# in_board.net
KiCad netlist of a schematic drawn in Altium Designer
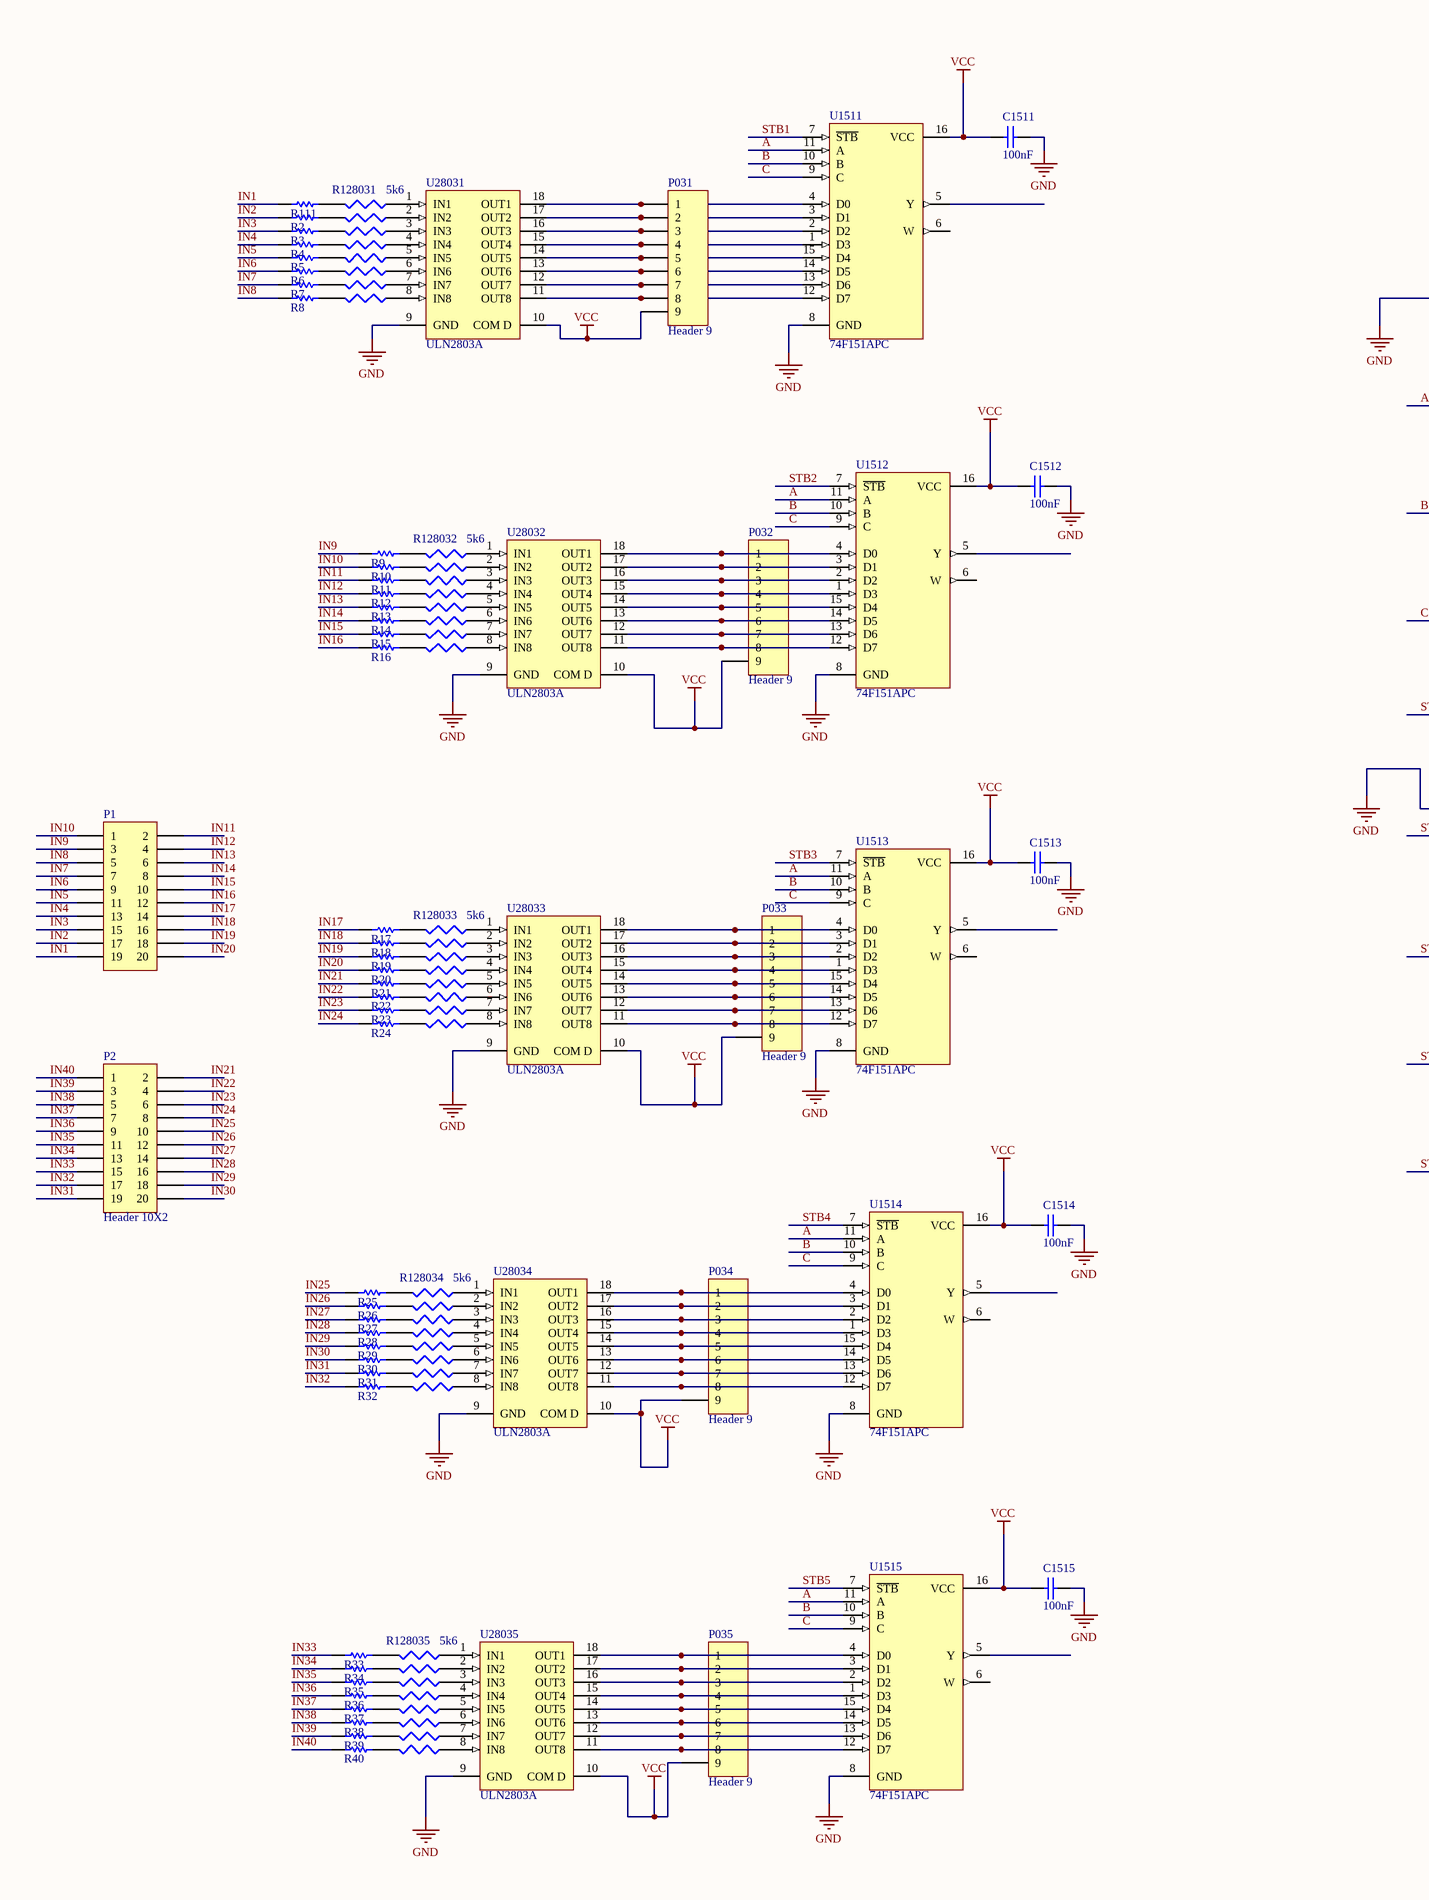
[diagram p0: in_board.SchDoc, left]
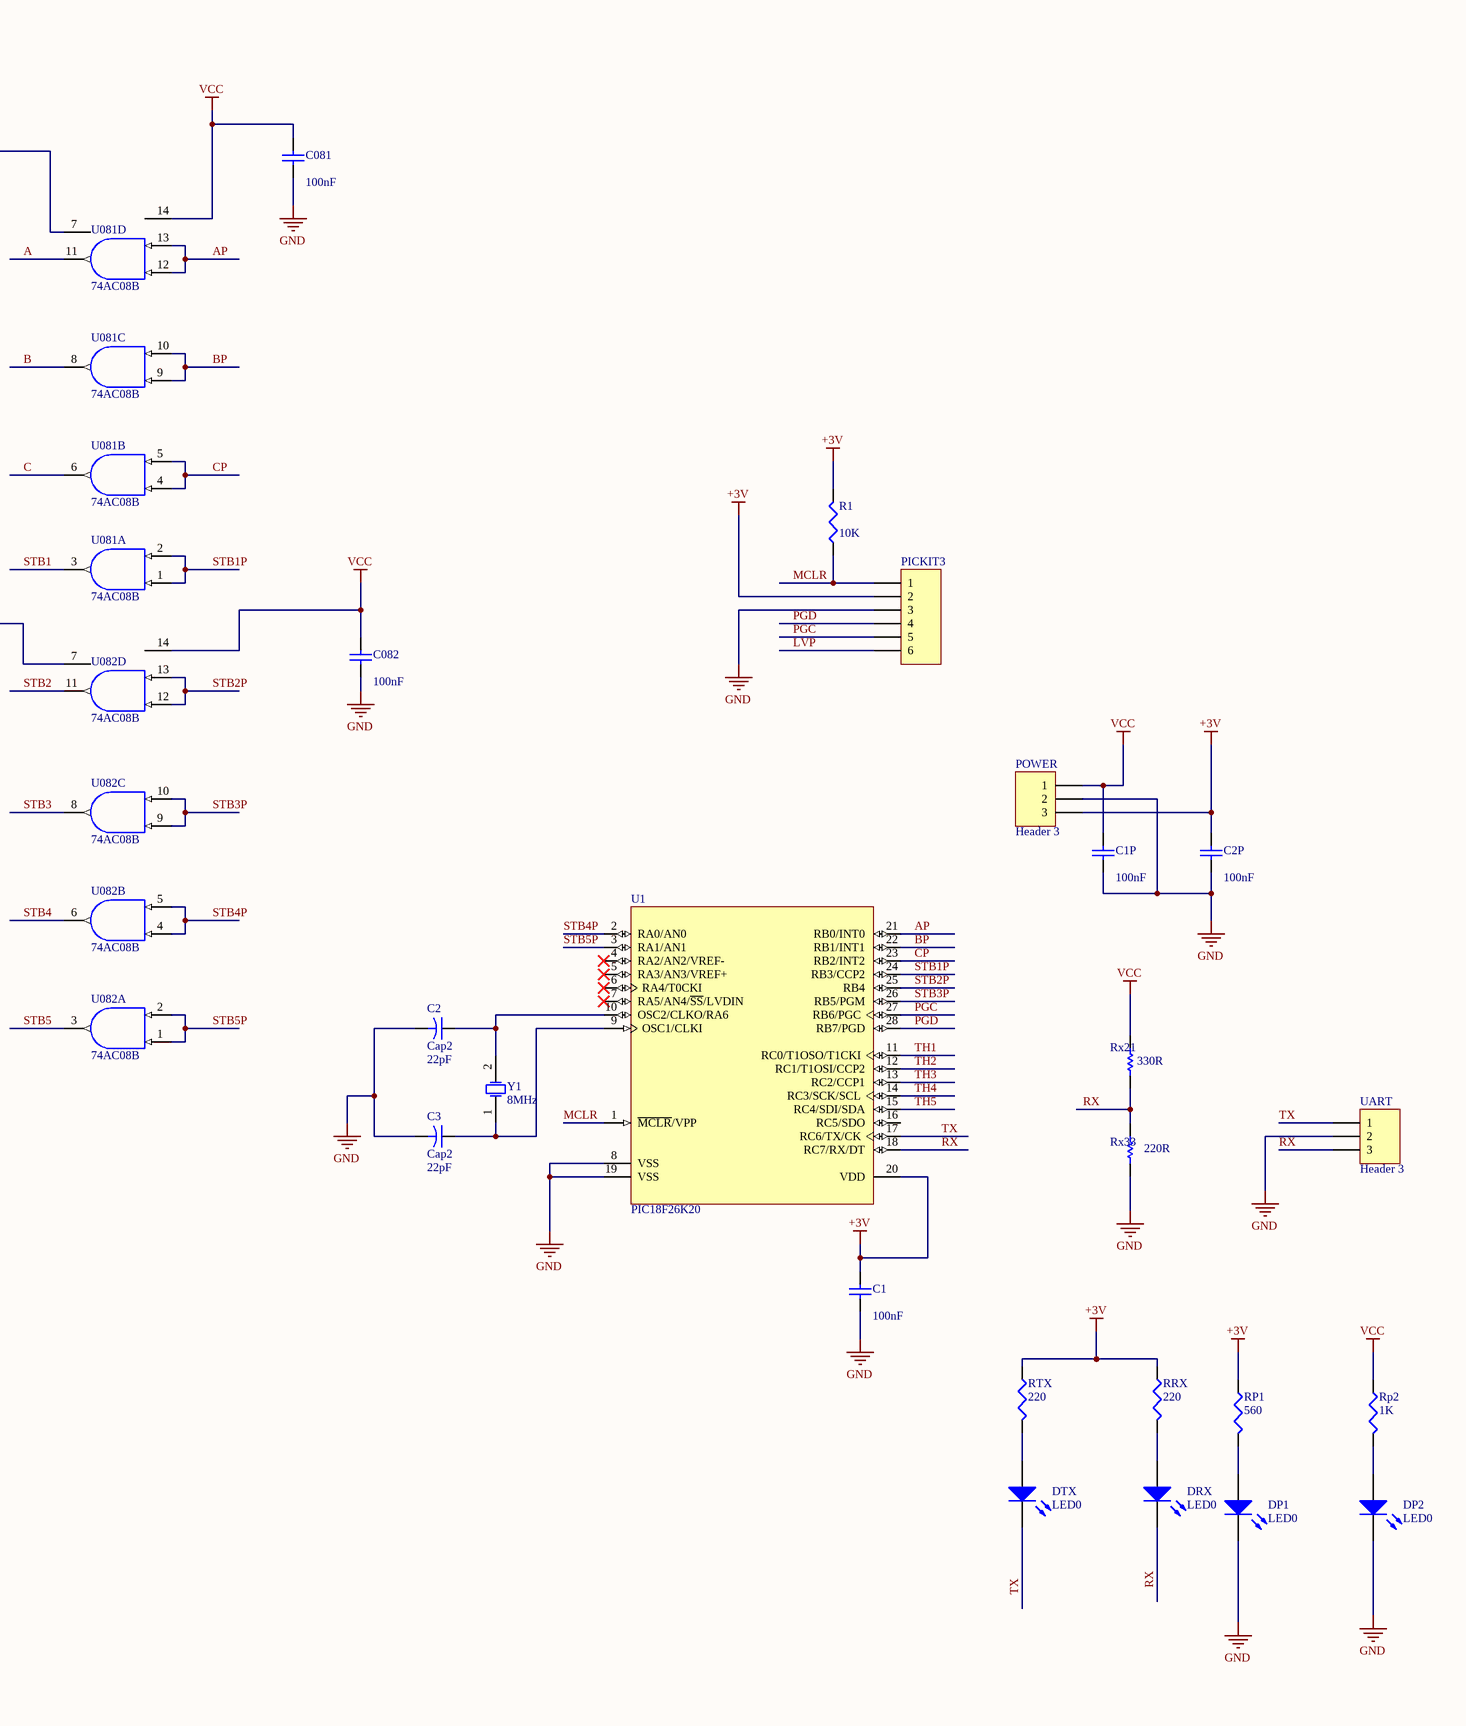
[diagram p1: in_board.SchDoc, right]

(export (version "E")
  (design (tool "Eeschema 10.0.6"))
  (components
    (comp (ref "C1")
      (value "100nF")
      (footprint "Device:tu_gom")
      (description "Capacitor")
      (fields (field (name "Comment") "Cap") (field (name "PUBLISHER") "Altium Limited"))
      (libsource (lib "Miscellaneous Devices") (part "Cap"))
    )
    (comp (ref "C1P")
      (value "100nF")
      (footprint "Device:tu_gom")
      (description "Capacitor")
      (fields (field (name "Comment") "Cap") (field (name "PUBLISHER") "Altium Limited"))
      (libsource (lib "Miscellaneous Devices") (part "Cap"))
    )
    (comp (ref "C2")
      (value "Cap2")
      (footprint "Device:tu_gom")
      (description "Capacitor")
      (fields (field (name "ALTIUM_VALUE") "22pF") (field (name "PUBLISHER") "Altium Limited"))
      (libsource (lib "Miscellaneous Devices") (part "Cap2"))
    )
    (comp (ref "C2P")
      (value "100nF")
      (footprint "Device:tu_gom")
      (description "Capacitor")
      (fields (field (name "Comment") "Cap") (field (name "PUBLISHER") "Altium Limited"))
      (libsource (lib "Miscellaneous Devices") (part "Cap"))
    )
    (comp (ref "C3")
      (value "Cap2")
      (footprint "Device:tu_gom")
      (description "Capacitor")
      (fields (field (name "ALTIUM_VALUE") "22pF") (field (name "PUBLISHER") "Altium Limited"))
      (libsource (lib "Miscellaneous Devices") (part "Cap2"))
    )
    (comp (ref "C081")
      (value "100nF")
      (footprint "Device:tu_gom")
      (description "Capacitor")
      (fields (field (name "Comment") "Cap") (field (name "PUBLISHER") "Altium Limited"))
      (libsource (lib "Miscellaneous Devices") (part "Cap"))
    )
    (comp (ref "C082")
      (value "100nF")
      (footprint "Device:tu_gom")
      (description "Capacitor")
      (fields (field (name "Comment") "Cap") (field (name "PUBLISHER") "Altium Limited"))
      (libsource (lib "Miscellaneous Devices") (part "Cap"))
    )
    (comp (ref "C1511")
      (value "100nF")
      (footprint "Device:tu_gom")
      (description "Capacitor")
      (fields (field (name "Comment") "Cap") (field (name "PUBLISHER") "Altium Limited"))
      (libsource (lib "Miscellaneous Devices") (part "Cap"))
    )
    (comp (ref "C1512")
      (value "100nF")
      (footprint "Device:tu_gom")
      (description "Capacitor")
      (fields (field (name "Comment") "Cap") (field (name "PUBLISHER") "Altium Limited"))
      (libsource (lib "Miscellaneous Devices") (part "Cap"))
    )
    (comp (ref "C1513")
      (value "100nF")
      (footprint "Device:tu_gom")
      (description "Capacitor")
      (fields (field (name "Comment") "Cap") (field (name "PUBLISHER") "Altium Limited"))
      (libsource (lib "Miscellaneous Devices") (part "Cap"))
    )
    (comp (ref "C1514")
      (value "100nF")
      (footprint "Device:tu_gom")
      (description "Capacitor")
      (fields (field (name "Comment") "Cap") (field (name "PUBLISHER") "Altium Limited"))
      (libsource (lib "Miscellaneous Devices") (part "Cap"))
    )
    (comp (ref "C1515")
      (value "100nF")
      (footprint "Device:tu_gom")
      (description "Capacitor")
      (fields (field (name "Comment") "Cap") (field (name "PUBLISHER") "Altium Limited"))
      (libsource (lib "Miscellaneous Devices") (part "Cap"))
    )
    (comp (ref "DP1")
      (value "LED0")
      (footprint "Device:LED_3")
      (description "Typical INFRARED GaAs LED")
      (fields (field (name "PUBLISHER") "Altium Limited"))
      (libsource (lib "Miscellaneous Devices") (part "LED0"))
    )
    (comp (ref "DP2")
      (value "LED0")
      (footprint "Device:LED_3")
      (description "Typical INFRARED GaAs LED")
      (fields (field (name "PUBLISHER") "Altium Limited"))
      (libsource (lib "Miscellaneous Devices") (part "LED0"))
    )
    (comp (ref "DRX")
      (value "LED0")
      (footprint "Device:LED_3")
      (description "Typical INFRARED GaAs LED")
      (fields (field (name "PUBLISHER") "Altium Limited"))
      (libsource (lib "Miscellaneous Devices") (part "LED0"))
    )
    (comp (ref "DTX")
      (value "LED0")
      (footprint "Device:LED_3")
      (description "Typical INFRARED GaAs LED")
      (fields (field (name "PUBLISHER") "Altium Limited"))
      (libsource (lib "Miscellaneous Devices") (part "LED0"))
    )
    (comp (ref "P1")
      (value "Header 10X2")
      (footprint "HDR2X10")
      (description "Header, 10-Pin, Dual row")
      (fields (field (name "PUBLISHER") "Altium Limited"))
      (libsource (lib "Miscellaneous Connectors") (part "Header 10X2"))
    )
    (comp (ref "P2")
      (value "Header 10X2")
      (footprint "HDR2X10")
      (description "Header, 10-Pin, Dual row")
      (fields (field (name "PUBLISHER") "Altium Limited"))
      (libsource (lib "Miscellaneous Connectors") (part "Header 10X2"))
    )
    (comp (ref "P031")
      (value "Header 9")
      (footprint "HDR1X9")
      (description "Header, 9-Pin")
      (fields (field (name "PUBLISHER") "Altium Limited"))
      (libsource (lib "Miscellaneous Connectors") (part "Header 9"))
    )
    (comp (ref "P032")
      (value "Header 9")
      (footprint "HDR1X9")
      (description "Header, 9-Pin")
      (fields (field (name "PUBLISHER") "Altium Limited"))
      (libsource (lib "Miscellaneous Connectors") (part "Header 9"))
    )
    (comp (ref "P033")
      (value "Header 9")
      (footprint "HDR1X9")
      (description "Header, 9-Pin")
      (fields (field (name "PUBLISHER") "Altium Limited"))
      (libsource (lib "Miscellaneous Connectors") (part "Header 9"))
    )
    (comp (ref "P034")
      (value "Header 9")
      (footprint "HDR1X9")
      (description "Header, 9-Pin")
      (fields (field (name "PUBLISHER") "Altium Limited"))
      (libsource (lib "Miscellaneous Connectors") (part "Header 9"))
    )
    (comp (ref "P035")
      (value "Header 9")
      (footprint "HDR1X9")
      (description "Header, 9-Pin")
      (fields (field (name "PUBLISHER") "Altium Limited"))
      (libsource (lib "Miscellaneous Connectors") (part "Header 9"))
    )
    (comp (ref "PICKIT3")
      (value "PICKIT3")
      (footprint "HDR1X6")
      (description "Header, 6-Pin")
      (fields (field (name "PUBLISHER") "Altium Limited"))
      (libsource (lib "Miscellaneous Connectors") (part "Header 6"))
    )
    (comp (ref "POWER")
      (value "Header 3")
      (footprint "Device:HEADER3")
      (description "Header, 3-Pin")
      (fields (field (name "PUBLISHER") "Altium Limited"))
      (libsource (lib "Miscellaneous Connectors") (part "Header 3"))
    )
    (comp (ref "R1")
      (value "10K")
      (footprint "Device:R_Nor")
      (description "Resistor")
      (fields (field (name "Comment") "Res3") (field (name "PUBLISHER") "Altium Limited"))
      (libsource (lib "Miscellaneous Devices") (part "Res3"))
    )
    (comp (ref "R2")
      (value "Res")
      (footprint "Device:R_Nor")
      (libsource (lib "Device_Component") (part "Res"))
    )
    (comp (ref "R3")
      (value "Res")
      (footprint "Device:R_Nor")
      (libsource (lib "Device_Component") (part "Res"))
    )
    (comp (ref "R4")
      (value "Res")
      (footprint "Device:R_Nor")
      (libsource (lib "Device_Component") (part "Res"))
    )
    (comp (ref "R5")
      (value "Res")
      (footprint "Device:R_Nor")
      (libsource (lib "Device_Component") (part "Res"))
    )
    (comp (ref "R6")
      (value "Res")
      (footprint "Device:R_Nor")
      (libsource (lib "Device_Component") (part "Res"))
    )
    (comp (ref "R7")
      (value "Res")
      (footprint "Device:R_Nor")
      (libsource (lib "Device_Component") (part "Res"))
    )
    (comp (ref "R8")
      (value "Res")
      (footprint "Device:R_Nor")
      (libsource (lib "Device_Component") (part "Res"))
    )
    (comp (ref "R9")
      (value "Res")
      (footprint "Device:R_Nor")
      (libsource (lib "Device_Component") (part "Res"))
    )
    (comp (ref "R10")
      (value "Res")
      (footprint "Device:R_Nor")
      (libsource (lib "Device_Component") (part "Res"))
    )
    (comp (ref "R11")
      (value "Res")
      (footprint "Device:R_Nor")
      (libsource (lib "Device_Component") (part "Res"))
    )
    (comp (ref "R12")
      (value "Res")
      (footprint "Device:R_Nor")
      (libsource (lib "Device_Component") (part "Res"))
    )
    (comp (ref "R13")
      (value "Res")
      (footprint "Device:R_Nor")
      (libsource (lib "Device_Component") (part "Res"))
    )
    (comp (ref "R14")
      (value "Res")
      (footprint "Device:R_Nor")
      (libsource (lib "Device_Component") (part "Res"))
    )
    (comp (ref "R15")
      (value "Res")
      (footprint "Device:R_Nor")
      (libsource (lib "Device_Component") (part "Res"))
    )
    (comp (ref "R16")
      (value "Res")
      (footprint "Device:R_Nor")
      (libsource (lib "Device_Component") (part "Res"))
    )
    (comp (ref "R17")
      (value "Res")
      (footprint "Device:R_Nor")
      (libsource (lib "Device_Component") (part "Res"))
    )
    (comp (ref "R18")
      (value "Res")
      (footprint "Device:R_Nor")
      (libsource (lib "Device_Component") (part "Res"))
    )
    (comp (ref "R19")
      (value "Res")
      (footprint "Device:R_Nor")
      (libsource (lib "Device_Component") (part "Res"))
    )
    (comp (ref "R20")
      (value "Res")
      (footprint "Device:R_Nor")
      (libsource (lib "Device_Component") (part "Res"))
    )
    (comp (ref "R21")
      (value "Res")
      (footprint "Device:R_Nor")
      (libsource (lib "Device_Component") (part "Res"))
    )
    (comp (ref "R22")
      (value "Res")
      (footprint "Device:R_Nor")
      (libsource (lib "Device_Component") (part "Res"))
    )
    (comp (ref "R23")
      (value "Res")
      (footprint "Device:R_Nor")
      (libsource (lib "Device_Component") (part "Res"))
    )
    (comp (ref "R24")
      (value "Res")
      (footprint "Device:R_Nor")
      (libsource (lib "Device_Component") (part "Res"))
    )
    (comp (ref "R25")
      (value "Res")
      (footprint "Device:R_Nor")
      (libsource (lib "Device_Component") (part "Res"))
    )
    (comp (ref "R26")
      (value "Res")
      (footprint "Device:R_Nor")
      (libsource (lib "Device_Component") (part "Res"))
    )
    (comp (ref "R27")
      (value "Res")
      (footprint "Device:R_Nor")
      (libsource (lib "Device_Component") (part "Res"))
    )
    (comp (ref "R28")
      (value "Res")
      (footprint "Device:R_Nor")
      (libsource (lib "Device_Component") (part "Res"))
    )
    (comp (ref "R29")
      (value "Res")
      (footprint "Device:R_Nor")
      (libsource (lib "Device_Component") (part "Res"))
    )
    (comp (ref "R30")
      (value "Res")
      (footprint "Device:R_Nor")
      (libsource (lib "Device_Component") (part "Res"))
    )
    (comp (ref "R31")
      (value "Res")
      (footprint "Device:R_Nor")
      (libsource (lib "Device_Component") (part "Res"))
    )
    (comp (ref "R32")
      (value "Res")
      (footprint "Device:R_Nor")
      (libsource (lib "Device_Component") (part "Res"))
    )
    (comp (ref "R33")
      (value "Res")
      (footprint "Device:R_Nor")
      (libsource (lib "Device_Component") (part "Res"))
    )
    (comp (ref "R34")
      (value "Res")
      (footprint "Device:R_Nor")
      (libsource (lib "Device_Component") (part "Res"))
    )
    (comp (ref "R35")
      (value "Res")
      (footprint "Device:R_Nor")
      (libsource (lib "Device_Component") (part "Res"))
    )
    (comp (ref "R36")
      (value "Res")
      (footprint "Device:R_Nor")
      (libsource (lib "Device_Component") (part "Res"))
    )
    (comp (ref "R37")
      (value "Res")
      (footprint "Device:R_Nor")
      (libsource (lib "Device_Component") (part "Res"))
    )
    (comp (ref "R38")
      (value "Res")
      (footprint "Device:R_Nor")
      (libsource (lib "Device_Component") (part "Res"))
    )
    (comp (ref "R39")
      (value "Res")
      (footprint "Device:R_Nor")
      (libsource (lib "Device_Component") (part "Res"))
    )
    (comp (ref "R40")
      (value "Res")
      (footprint "Device:R_Nor")
      (libsource (lib "Device_Component") (part "Res"))
    )
    (comp (ref "R111")
      (value "Res")
      (footprint "Device:R_Nor")
      (libsource (lib "Device_Component") (part "Res"))
    )
    (comp (ref "R42802")
      (value "Res3")
      (footprint "Device:R_Nor")
      (description "Resistor")
      (fields (field (name "PUBLISHER") "Altium Limited"))
      (libsource (lib "Miscellaneous Devices") (part "Res3"))
    )
    (comp (ref "R42803")
      (value "Res3")
      (footprint "Device:R_Nor")
      (description "Resistor")
      (fields (field (name "PUBLISHER") "Altium Limited"))
      (libsource (lib "Miscellaneous Devices") (part "Res3"))
    )
    (comp (ref "R42804")
      (value "Res3")
      (footprint "Device:R_Nor")
      (description "Resistor")
      (fields (field (name "PUBLISHER") "Altium Limited"))
      (libsource (lib "Miscellaneous Devices") (part "Res3"))
    )
    (comp (ref "R128031")
      (value "5k6")
      (footprint "Device:R_Nor")
      (description "Resistor")
      (fields (field (name "Comment") "Res3") (field (name "PUBLISHER") "Altium Limited"))
      (libsource (lib "Miscellaneous Devices") (part "Res3"))
    )
    (comp (ref "R128032")
      (value "5k6")
      (footprint "Device:R_Nor")
      (description "Resistor")
      (fields (field (name "Comment") "Res3") (field (name "PUBLISHER") "Altium Limited"))
      (libsource (lib "Miscellaneous Devices") (part "Res3"))
    )
    (comp (ref "R128033")
      (value "5k6")
      (footprint "Device:R_Nor")
      (description "Resistor")
      (fields (field (name "Comment") "Res3") (field (name "PUBLISHER") "Altium Limited"))
      (libsource (lib "Miscellaneous Devices") (part "Res3"))
    )
    (comp (ref "R128034")
      (value "5k6")
      (footprint "Device:R_Nor")
      (description "Resistor")
      (fields (field (name "Comment") "Res3") (field (name "PUBLISHER") "Altium Limited"))
      (libsource (lib "Miscellaneous Devices") (part "Res3"))
    )
    (comp (ref "R128035")
      (value "5k6")
      (footprint "Device:R_Nor")
      (description "Resistor")
      (fields (field (name "Comment") "Res3") (field (name "PUBLISHER") "Altium Limited"))
      (libsource (lib "Miscellaneous Devices") (part "Res3"))
    )
    (comp (ref "R228031")
      (value "Res3")
      (footprint "Device:R_Nor")
      (description "Resistor")
      (fields (field (name "PUBLISHER") "Altium Limited"))
      (libsource (lib "Miscellaneous Devices") (part "Res3"))
    )
    (comp (ref "R228032")
      (value "Res3")
      (footprint "Device:R_Nor")
      (description "Resistor")
      (fields (field (name "PUBLISHER") "Altium Limited"))
      (libsource (lib "Miscellaneous Devices") (part "Res3"))
    )
    (comp (ref "R228033")
      (value "Res3")
      (footprint "Device:R_Nor")
      (description "Resistor")
      (fields (field (name "PUBLISHER") "Altium Limited"))
      (libsource (lib "Miscellaneous Devices") (part "Res3"))
    )
    (comp (ref "R228034")
      (value "Res3")
      (footprint "Device:R_Nor")
      (description "Resistor")
      (fields (field (name "PUBLISHER") "Altium Limited"))
      (libsource (lib "Miscellaneous Devices") (part "Res3"))
    )
    (comp (ref "R228035")
      (value "Res3")
      (footprint "Device:R_Nor")
      (description "Resistor")
      (fields (field (name "PUBLISHER") "Altium Limited"))
      (libsource (lib "Miscellaneous Devices") (part "Res3"))
    )
    (comp (ref "R328031")
      (value "Res3")
      (footprint "Device:R_Nor")
      (description "Resistor")
      (fields (field (name "PUBLISHER") "Altium Limited"))
      (libsource (lib "Miscellaneous Devices") (part "Res3"))
    )
    (comp (ref "R328032")
      (value "Res3")
      (footprint "Device:R_Nor")
      (description "Resistor")
      (fields (field (name "PUBLISHER") "Altium Limited"))
      (libsource (lib "Miscellaneous Devices") (part "Res3"))
    )
    (comp (ref "R328033")
      (value "Res3")
      (footprint "Device:R_Nor")
      (description "Resistor")
      (fields (field (name "PUBLISHER") "Altium Limited"))
      (libsource (lib "Miscellaneous Devices") (part "Res3"))
    )
    (comp (ref "R328034")
      (value "Res3")
      (footprint "Device:R_Nor")
      (description "Resistor")
      (fields (field (name "PUBLISHER") "Altium Limited"))
      (libsource (lib "Miscellaneous Devices") (part "Res3"))
    )
    (comp (ref "R328035")
      (value "Res3")
      (footprint "Device:R_Nor")
      (description "Resistor")
      (fields (field (name "PUBLISHER") "Altium Limited"))
      (libsource (lib "Miscellaneous Devices") (part "Res3"))
    )
    (comp (ref "R428031")
      (value "Res3")
      (footprint "Device:R_Nor")
      (description "Resistor")
      (fields (field (name "PUBLISHER") "Altium Limited"))
      (libsource (lib "Miscellaneous Devices") (part "Res3"))
    )
    (comp (ref "R428035")
      (value "Res3")
      (footprint "Device:R_Nor")
      (description "Resistor")
      (fields (field (name "PUBLISHER") "Altium Limited"))
      (libsource (lib "Miscellaneous Devices") (part "Res3"))
    )
    (comp (ref "R528031")
      (value "Res3")
      (footprint "Device:R_Nor")
      (description "Resistor")
      (fields (field (name "PUBLISHER") "Altium Limited"))
      (libsource (lib "Miscellaneous Devices") (part "Res3"))
    )
    (comp (ref "R528032")
      (value "Res3")
      (footprint "Device:R_Nor")
      (description "Resistor")
      (fields (field (name "PUBLISHER") "Altium Limited"))
      (libsource (lib "Miscellaneous Devices") (part "Res3"))
    )
    (comp (ref "R528033")
      (value "Res3")
      (footprint "Device:R_Nor")
      (description "Resistor")
      (fields (field (name "PUBLISHER") "Altium Limited"))
      (libsource (lib "Miscellaneous Devices") (part "Res3"))
    )
    (comp (ref "R528034")
      (value "Res3")
      (footprint "Device:R_Nor")
      (description "Resistor")
      (fields (field (name "PUBLISHER") "Altium Limited"))
      (libsource (lib "Miscellaneous Devices") (part "Res3"))
    )
    (comp (ref "R528035")
      (value "Res3")
      (footprint "Device:R_Nor")
      (description "Resistor")
      (fields (field (name "PUBLISHER") "Altium Limited"))
      (libsource (lib "Miscellaneous Devices") (part "Res3"))
    )
    (comp (ref "R628031")
      (value "Res3")
      (footprint "Device:R_Nor")
      (description "Resistor")
      (fields (field (name "PUBLISHER") "Altium Limited"))
      (libsource (lib "Miscellaneous Devices") (part "Res3"))
    )
    (comp (ref "R628032")
      (value "Res3")
      (footprint "Device:R_Nor")
      (description "Resistor")
      (fields (field (name "PUBLISHER") "Altium Limited"))
      (libsource (lib "Miscellaneous Devices") (part "Res3"))
    )
    (comp (ref "R628033")
      (value "Res3")
      (footprint "Device:R_Nor")
      (description "Resistor")
      (fields (field (name "PUBLISHER") "Altium Limited"))
      (libsource (lib "Miscellaneous Devices") (part "Res3"))
    )
    (comp (ref "R628034")
      (value "Res3")
      (footprint "Device:R_Nor")
      (description "Resistor")
      (fields (field (name "PUBLISHER") "Altium Limited"))
      (libsource (lib "Miscellaneous Devices") (part "Res3"))
    )
    (comp (ref "R628035")
      (value "Res3")
      (footprint "Device:R_Nor")
      (description "Resistor")
      (fields (field (name "PUBLISHER") "Altium Limited"))
      (libsource (lib "Miscellaneous Devices") (part "Res3"))
    )
    (comp (ref "R728031")
      (value "Res3")
      (footprint "Device:R_Nor")
      (description "Resistor")
      (fields (field (name "PUBLISHER") "Altium Limited"))
      (libsource (lib "Miscellaneous Devices") (part "Res3"))
    )
    (comp (ref "R728032")
      (value "Res3")
      (footprint "Device:R_Nor")
      (description "Resistor")
      (fields (field (name "PUBLISHER") "Altium Limited"))
      (libsource (lib "Miscellaneous Devices") (part "Res3"))
    )
    (comp (ref "R728033")
      (value "Res3")
      (footprint "Device:R_Nor")
      (description "Resistor")
      (fields (field (name "PUBLISHER") "Altium Limited"))
      (libsource (lib "Miscellaneous Devices") (part "Res3"))
    )
    (comp (ref "R728034")
      (value "Res3")
      (footprint "Device:R_Nor")
      (description "Resistor")
      (fields (field (name "PUBLISHER") "Altium Limited"))
      (libsource (lib "Miscellaneous Devices") (part "Res3"))
    )
    (comp (ref "R728035")
      (value "Res3")
      (footprint "Device:R_Nor")
      (description "Resistor")
      (fields (field (name "PUBLISHER") "Altium Limited"))
      (libsource (lib "Miscellaneous Devices") (part "Res3"))
    )
    (comp (ref "R828031")
      (value "Res3")
      (footprint "Device:R_Nor")
      (description "Resistor")
      (fields (field (name "PUBLISHER") "Altium Limited"))
      (libsource (lib "Miscellaneous Devices") (part "Res3"))
    )
    (comp (ref "R828032")
      (value "Res3")
      (footprint "Device:R_Nor")
      (description "Resistor")
      (fields (field (name "PUBLISHER") "Altium Limited"))
      (libsource (lib "Miscellaneous Devices") (part "Res3"))
    )
    (comp (ref "R828033")
      (value "Res3")
      (footprint "Device:R_Nor")
      (description "Resistor")
      (fields (field (name "PUBLISHER") "Altium Limited"))
      (libsource (lib "Miscellaneous Devices") (part "Res3"))
    )
    (comp (ref "R828034")
      (value "Res3")
      (footprint "Device:R_Nor")
      (description "Resistor")
      (fields (field (name "PUBLISHER") "Altium Limited"))
      (libsource (lib "Miscellaneous Devices") (part "Res3"))
    )
    (comp (ref "R828035")
      (value "Res3")
      (footprint "Device:R_Nor")
      (description "Resistor")
      (fields (field (name "PUBLISHER") "Altium Limited"))
      (libsource (lib "Miscellaneous Devices") (part "Res3"))
    )
    (comp (ref "RP1")
      (value "560")
      (footprint "Device:R_Nor")
      (description "Resistor")
      (fields (field (name "Comment") "Res3") (field (name "PUBLISHER") "Altium Limited"))
      (libsource (lib "Miscellaneous Devices") (part "Res3"))
    )
    (comp (ref "Rp2")
      (value "1K")
      (footprint "Device:R_Nor")
      (description "Resistor")
      (fields (field (name "Comment") "Res3") (field (name "PUBLISHER") "Altium Limited"))
      (libsource (lib "Miscellaneous Devices") (part "Res3"))
    )
    (comp (ref "RRX")
      (value "220")
      (footprint "Device:R_Nor")
      (description "Resistor")
      (fields (field (name "Comment") "Res3") (field (name "PUBLISHER") "Altium Limited"))
      (libsource (lib "Miscellaneous Devices") (part "Res3"))
    )
    (comp (ref "RTX")
      (value "220")
      (footprint "Device:R_Nor")
      (description "Resistor")
      (fields (field (name "Comment") "Res3") (field (name "PUBLISHER") "Altium Limited"))
      (libsource (lib "Miscellaneous Devices") (part "Res3"))
    )
    (comp (ref "Rx21")
      (value "330R")
      (footprint "Device:R_Nor")
      (libsource (lib "Device_Component") (part "Res"))
    )
    (comp (ref "Rx33")
      (value "220R")
      (footprint "Device:R_Nor")
      (libsource (lib "Device_Component") (part "Res"))
    )
    (comp (ref "U1")
      (value "PIC18F26K20")
      (footprint "SOIC300-28_N")
      (fields (field (name "PUBLISHER") "Altium Limited"))
      (libsource (lib "Microchip Microcontroller 8-Bit PIC18") (part "PIC18F242-E/SO"))
    )
    (comp (ref "U081")
      (value "74AC08B")
      (footprint "DIP14")
      (description "Quad 2-Input AND Gate")
      (fields (field (name "PUBLISHER") "Altium Limited"))
      (libsource (lib "ST Logic Gate") (part "74AC08B"))
    )
    (comp (ref "U082")
      (value "74AC08B")
      (footprint "DIP14")
      (description "Quad 2-Input AND Gate")
      (fields (field (name "PUBLISHER") "Altium Limited"))
      (libsource (lib "ST Logic Gate") (part "74AC08B"))
    )
    (comp (ref "U1511")
      (value "74F151APC")
      (footprint "N16E")
      (description "8-Input Multiplexer")
      (fields (field (name "PUBLISHER") "Altium Limited"))
      (libsource (lib "NSC Logic Multiplexer") (part "74F151APC"))
    )
    (comp (ref "U1512")
      (value "74F151APC")
      (footprint "N16E")
      (description "8-Input Multiplexer")
      (fields (field (name "PUBLISHER") "Altium Limited"))
      (libsource (lib "NSC Logic Multiplexer") (part "74F151APC"))
    )
    (comp (ref "U1513")
      (value "74F151APC")
      (footprint "N16E")
      (description "8-Input Multiplexer")
      (fields (field (name "PUBLISHER") "Altium Limited"))
      (libsource (lib "NSC Logic Multiplexer") (part "74F151APC"))
    )
    (comp (ref "U1514")
      (value "74F151APC")
      (footprint "N16E")
      (description "8-Input Multiplexer")
      (fields (field (name "PUBLISHER") "Altium Limited"))
      (libsource (lib "NSC Logic Multiplexer") (part "74F151APC"))
    )
    (comp (ref "U1515")
      (value "74F151APC")
      (footprint "N16E")
      (description "8-Input Multiplexer")
      (fields (field (name "PUBLISHER") "Altium Limited"))
      (libsource (lib "NSC Logic Multiplexer") (part "74F151APC"))
    )
    (comp (ref "U28031")
      (value "ULN2803A")
      (footprint "DIP18")
      (description "Eight Darlington Array")
      (fields (field (name "PUBLISHER") "Altium Limited"))
      (libsource (lib "ST Interface Darlington Driver") (part "ULN2803A"))
    )
    (comp (ref "U28032")
      (value "ULN2803A")
      (footprint "DIP18")
      (description "Eight Darlington Array")
      (fields (field (name "PUBLISHER") "Altium Limited"))
      (libsource (lib "ST Interface Darlington Driver") (part "ULN2803A"))
    )
    (comp (ref "U28033")
      (value "ULN2803A")
      (footprint "DIP18")
      (description "Eight Darlington Array")
      (fields (field (name "PUBLISHER") "Altium Limited"))
      (libsource (lib "ST Interface Darlington Driver") (part "ULN2803A"))
    )
    (comp (ref "U28034")
      (value "ULN2803A")
      (footprint "DIP18")
      (description "Eight Darlington Array")
      (fields (field (name "PUBLISHER") "Altium Limited"))
      (libsource (lib "ST Interface Darlington Driver") (part "ULN2803A"))
    )
    (comp (ref "U28035")
      (value "ULN2803A")
      (footprint "DIP18")
      (description "Eight Darlington Array")
      (fields (field (name "PUBLISHER") "Altium Limited"))
      (libsource (lib "ST Interface Darlington Driver") (part "ULN2803A"))
    )
    (comp (ref "UART")
      (value "Header 3")
      (footprint "Device:Coc3_15A")
      (description "Header, 3-Pin")
      (fields (field (name "PUBLISHER") "Altium Limited"))
      (libsource (lib "") (part "Header 3_1"))
    )
    (comp (ref "Y1")
      (value "8MHz")
      (footprint "Device:Xtal12M")
      (description "Crystal Oscillator")
      (fields (field (name "PUBLISHER") "Altium Limited"))
      (libsource (lib "Miscellaneous Devices") (part "XTAL"))
    )
  )
  (nets
    (net (code "1") (name "+3V") (class "Default")
      (node (ref "C1") (pin "1") (pinfunction "1_1") (pintype "passive"))
      (node (ref "C2P") (pin "1") (pinfunction "1_1") (pintype "passive"))
      (node (ref "PICKIT3") (pin "2") (pinfunction "2_2") (pintype "passive"))
      (node (ref "POWER") (pin "3") (pinfunction "3_3") (pintype "passive"))
      (node (ref "R1") (pin "2") (pinfunction "2_2") (pintype "passive"))
      (node (ref "RP1") (pin "1") (pinfunction "1_1") (pintype "passive"))
      (node (ref "RRX") (pin "1") (pinfunction "1_1") (pintype "passive"))
      (node (ref "RTX") (pin "1") (pinfunction "1_1") (pintype "passive"))
      (node (ref "U1") (pin "20") (pinfunction "VDD_20") (pintype "power_in"))
    )
    (net (code "2") (name "/A") (class "Default")
      (node (ref "U081") (pin "11") (pinfunction "Y_11") (pintype "output"))
      (node (ref "U1511") (pin "11") (pinfunction "A_11") (pintype "input"))
      (node (ref "U1512") (pin "11") (pinfunction "A_11") (pintype "input"))
      (node (ref "U1513") (pin "11") (pinfunction "A_11") (pintype "input"))
      (node (ref "U1514") (pin "11") (pinfunction "A_11") (pintype "input"))
      (node (ref "U1515") (pin "11") (pinfunction "A_11") (pintype "input"))
    )
    (net (code "3") (name "/AP") (class "Default")
      (node (ref "U081") (pin "12") (pinfunction "A_12") (pintype "input"))
      (node (ref "U081") (pin "13") (pinfunction "B_13") (pintype "input"))
      (node (ref "U1") (pin "21") (pinfunction "RB0/INT0_21") (pintype "bidirectional"))
    )
    (net (code "4") (name "/B") (class "Default")
      (node (ref "U081") (pin "8") (pinfunction "Y_8") (pintype "output"))
      (node (ref "U1511") (pin "10") (pinfunction "B_10") (pintype "input"))
      (node (ref "U1512") (pin "10") (pinfunction "B_10") (pintype "input"))
      (node (ref "U1513") (pin "10") (pinfunction "B_10") (pintype "input"))
      (node (ref "U1514") (pin "10") (pinfunction "B_10") (pintype "input"))
      (node (ref "U1515") (pin "10") (pinfunction "B_10") (pintype "input"))
    )
    (net (code "5") (name "/BP") (class "Default")
      (node (ref "U081") (pin "10") (pinfunction "B_10") (pintype "input"))
      (node (ref "U081") (pin "9") (pinfunction "A_9") (pintype "input"))
      (node (ref "U1") (pin "22") (pinfunction "RB1/INT1_22") (pintype "bidirectional"))
    )
    (net (code "6") (name "/C") (class "Default")
      (node (ref "U081") (pin "6") (pinfunction "Y_6") (pintype "output"))
      (node (ref "U1511") (pin "9") (pinfunction "C_9") (pintype "input"))
      (node (ref "U1512") (pin "9") (pinfunction "C_9") (pintype "input"))
      (node (ref "U1513") (pin "9") (pinfunction "C_9") (pintype "input"))
      (node (ref "U1514") (pin "9") (pinfunction "C_9") (pintype "input"))
      (node (ref "U1515") (pin "9") (pinfunction "C_9") (pintype "input"))
    )
    (net (code "7") (name "/CP") (class "Default")
      (node (ref "U081") (pin "4") (pinfunction "A_4") (pintype "input"))
      (node (ref "U081") (pin "5") (pinfunction "B_5") (pintype "input"))
      (node (ref "U1") (pin "23") (pinfunction "RB2/INT2_23") (pintype "bidirectional"))
    )
    (net (code "8") (name "/IN1") (class "Default")
      (node (ref "P1") (pin "19") (pinfunction "19_19") (pintype "passive"))
      (node (ref "R111") (pin "1") (pinfunction "1_1") (pintype "passive"))
    )
    (net (code "9") (name "/IN2") (class "Default")
      (node (ref "P1") (pin "17") (pinfunction "17_17") (pintype "passive"))
      (node (ref "R2") (pin "1") (pinfunction "1_1") (pintype "passive"))
    )
    (net (code "10") (name "/IN3") (class "Default")
      (node (ref "P1") (pin "15") (pinfunction "15_15") (pintype "passive"))
      (node (ref "R3") (pin "1") (pinfunction "1_1") (pintype "passive"))
    )
    (net (code "11") (name "/IN4") (class "Default")
      (node (ref "P1") (pin "13") (pinfunction "13_13") (pintype "passive"))
      (node (ref "R4") (pin "1") (pinfunction "1_1") (pintype "passive"))
    )
    (net (code "12") (name "/IN5") (class "Default")
      (node (ref "P1") (pin "11") (pinfunction "11_11") (pintype "passive"))
      (node (ref "R5") (pin "1") (pinfunction "1_1") (pintype "passive"))
    )
    (net (code "13") (name "/IN6") (class "Default")
      (node (ref "P1") (pin "9") (pinfunction "9_9") (pintype "passive"))
      (node (ref "R6") (pin "1") (pinfunction "1_1") (pintype "passive"))
    )
    (net (code "14") (name "/IN7") (class "Default")
      (node (ref "P1") (pin "7") (pinfunction "7_7") (pintype "passive"))
      (node (ref "R7") (pin "1") (pinfunction "1_1") (pintype "passive"))
    )
    (net (code "15") (name "/IN8") (class "Default")
      (node (ref "P1") (pin "5") (pinfunction "5_5") (pintype "passive"))
      (node (ref "R8") (pin "1") (pinfunction "1_1") (pintype "passive"))
    )
    (net (code "16") (name "/IN9") (class "Default")
      (node (ref "P1") (pin "3") (pinfunction "3_3") (pintype "passive"))
      (node (ref "R9") (pin "1") (pinfunction "1_1") (pintype "passive"))
    )
    (net (code "17") (name "/IN10") (class "Default")
      (node (ref "P1") (pin "1") (pinfunction "1_1") (pintype "passive"))
      (node (ref "R10") (pin "1") (pinfunction "1_1") (pintype "passive"))
    )
    (net (code "18") (name "/IN11") (class "Default")
      (node (ref "P1") (pin "2") (pinfunction "2_2") (pintype "passive"))
      (node (ref "R11") (pin "1") (pinfunction "1_1") (pintype "passive"))
    )
    (net (code "19") (name "/IN12") (class "Default")
      (node (ref "P1") (pin "4") (pinfunction "4_4") (pintype "passive"))
      (node (ref "R12") (pin "1") (pinfunction "1_1") (pintype "passive"))
    )
    (net (code "20") (name "/IN13") (class "Default")
      (node (ref "P1") (pin "6") (pinfunction "6_6") (pintype "passive"))
      (node (ref "R13") (pin "1") (pinfunction "1_1") (pintype "passive"))
    )
    (net (code "21") (name "/IN14") (class "Default")
      (node (ref "P1") (pin "8") (pinfunction "8_8") (pintype "passive"))
      (node (ref "R14") (pin "1") (pinfunction "1_1") (pintype "passive"))
    )
    (net (code "22") (name "/IN15") (class "Default")
      (node (ref "P1") (pin "10") (pinfunction "10_10") (pintype "passive"))
      (node (ref "R15") (pin "1") (pinfunction "1_1") (pintype "passive"))
    )
    (net (code "23") (name "/IN16") (class "Default")
      (node (ref "P1") (pin "12") (pinfunction "12_12") (pintype "passive"))
      (node (ref "R16") (pin "1") (pinfunction "1_1") (pintype "passive"))
    )
    (net (code "24") (name "/IN17") (class "Default")
      (node (ref "P1") (pin "14") (pinfunction "14_14") (pintype "passive"))
      (node (ref "R17") (pin "1") (pinfunction "1_1") (pintype "passive"))
    )
    (net (code "25") (name "/IN18") (class "Default")
      (node (ref "P1") (pin "16") (pinfunction "16_16") (pintype "passive"))
      (node (ref "R18") (pin "1") (pinfunction "1_1") (pintype "passive"))
    )
    (net (code "26") (name "/IN19") (class "Default")
      (node (ref "P1") (pin "18") (pinfunction "18_18") (pintype "passive"))
      (node (ref "R19") (pin "1") (pinfunction "1_1") (pintype "passive"))
    )
    (net (code "27") (name "/IN20") (class "Default")
      (node (ref "P1") (pin "20") (pinfunction "20_20") (pintype "passive"))
      (node (ref "R20") (pin "1") (pinfunction "1_1") (pintype "passive"))
    )
    (net (code "28") (name "/IN21") (class "Default")
      (node (ref "P2") (pin "2") (pinfunction "2_2") (pintype "passive"))
      (node (ref "R21") (pin "1") (pinfunction "1_1") (pintype "passive"))
    )
    (net (code "29") (name "/IN22") (class "Default")
      (node (ref "P2") (pin "4") (pinfunction "4_4") (pintype "passive"))
      (node (ref "R22") (pin "1") (pinfunction "1_1") (pintype "passive"))
    )
    (net (code "30") (name "/IN23") (class "Default")
      (node (ref "P2") (pin "6") (pinfunction "6_6") (pintype "passive"))
      (node (ref "R23") (pin "1") (pinfunction "1_1") (pintype "passive"))
    )
    (net (code "31") (name "/IN24") (class "Default")
      (node (ref "P2") (pin "8") (pinfunction "8_8") (pintype "passive"))
      (node (ref "R24") (pin "1") (pinfunction "1_1") (pintype "passive"))
    )
    (net (code "32") (name "/IN25") (class "Default")
      (node (ref "P2") (pin "10") (pinfunction "10_10") (pintype "passive"))
      (node (ref "R25") (pin "1") (pinfunction "1_1") (pintype "passive"))
    )
    (net (code "33") (name "/IN26") (class "Default")
      (node (ref "P2") (pin "12") (pinfunction "12_12") (pintype "passive"))
      (node (ref "R26") (pin "1") (pinfunction "1_1") (pintype "passive"))
    )
    (net (code "34") (name "/IN27") (class "Default")
      (node (ref "P2") (pin "14") (pinfunction "14_14") (pintype "passive"))
      (node (ref "R27") (pin "1") (pinfunction "1_1") (pintype "passive"))
    )
    (net (code "35") (name "/IN28") (class "Default")
      (node (ref "P2") (pin "16") (pinfunction "16_16") (pintype "passive"))
      (node (ref "R28") (pin "1") (pinfunction "1_1") (pintype "passive"))
    )
    (net (code "36") (name "/IN29") (class "Default")
      (node (ref "P2") (pin "18") (pinfunction "18_18") (pintype "passive"))
      (node (ref "R29") (pin "1") (pinfunction "1_1") (pintype "passive"))
    )
    (net (code "37") (name "/IN30") (class "Default")
      (node (ref "P2") (pin "20") (pinfunction "20_20") (pintype "passive"))
      (node (ref "R30") (pin "1") (pinfunction "1_1") (pintype "passive"))
    )
    (net (code "38") (name "/IN31") (class "Default")
      (node (ref "P2") (pin "19") (pinfunction "19_19") (pintype "passive"))
      (node (ref "R31") (pin "1") (pinfunction "1_1") (pintype "passive"))
    )
    (net (code "39") (name "/IN32") (class "Default")
      (node (ref "P2") (pin "17") (pinfunction "17_17") (pintype "passive"))
      (node (ref "R32") (pin "1") (pinfunction "1_1") (pintype "passive"))
    )
    (net (code "40") (name "/IN33") (class "Default")
      (node (ref "P2") (pin "15") (pinfunction "15_15") (pintype "passive"))
      (node (ref "R33") (pin "1") (pinfunction "1_1") (pintype "passive"))
    )
    (net (code "41") (name "/IN34") (class "Default")
      (node (ref "P2") (pin "13") (pinfunction "13_13") (pintype "passive"))
      (node (ref "R34") (pin "1") (pinfunction "1_1") (pintype "passive"))
    )
    (net (code "42") (name "/IN35") (class "Default")
      (node (ref "P2") (pin "11") (pinfunction "11_11") (pintype "passive"))
      (node (ref "R35") (pin "1") (pinfunction "1_1") (pintype "passive"))
    )
    (net (code "43") (name "/IN36") (class "Default")
      (node (ref "P2") (pin "9") (pinfunction "9_9") (pintype "passive"))
      (node (ref "R36") (pin "1") (pinfunction "1_1") (pintype "passive"))
    )
    (net (code "44") (name "/IN37") (class "Default")
      (node (ref "P2") (pin "7") (pinfunction "7_7") (pintype "passive"))
      (node (ref "R37") (pin "1") (pinfunction "1_1") (pintype "passive"))
    )
    (net (code "45") (name "/IN38") (class "Default")
      (node (ref "P2") (pin "5") (pinfunction "5_5") (pintype "passive"))
      (node (ref "R38") (pin "1") (pinfunction "1_1") (pintype "passive"))
    )
    (net (code "46") (name "/IN39") (class "Default")
      (node (ref "P2") (pin "3") (pinfunction "3_3") (pintype "passive"))
      (node (ref "R39") (pin "1") (pinfunction "1_1") (pintype "passive"))
    )
    (net (code "47") (name "/IN40") (class "Default")
      (node (ref "P2") (pin "1") (pinfunction "1_1") (pintype "passive"))
      (node (ref "R40") (pin "1") (pinfunction "1_1") (pintype "passive"))
    )
    (net (code "48") (name "/LVP") (class "Default")
      (node (ref "PICKIT3") (pin "6") (pinfunction "6_6") (pintype "passive"))
    )
    (net (code "49") (name "/MCLR") (class "Default")
      (node (ref "PICKIT3") (pin "1") (pinfunction "1_1") (pintype "passive"))
      (node (ref "R1") (pin "1") (pinfunction "1_1") (pintype "passive"))
      (node (ref "U1") (pin "1") (pinfunction "~{MCLR}/VPP_1") (pintype "input"))
    )
    (net (code "50") (name "/PGC") (class "Default")
      (node (ref "PICKIT3") (pin "5") (pinfunction "5_5") (pintype "passive"))
      (node (ref "U1") (pin "27") (pinfunction "RB6/PGC_27") (pintype "bidirectional"))
    )
    (net (code "51") (name "/PGD") (class "Default")
      (node (ref "PICKIT3") (pin "4") (pinfunction "4_4") (pintype "passive"))
      (node (ref "U1") (pin "28") (pinfunction "RB7/PGD_28") (pintype "bidirectional"))
    )
    (net (code "52") (name "/RX") (class "Default")
      (node (ref "DRX") (pin "2") (pinfunction "K_2") (pintype "passive"))
      (node (ref "Rx21") (pin "1") (pinfunction "1_1") (pintype "passive"))
      (node (ref "Rx33") (pin "2") (pinfunction "2_2") (pintype "passive"))
      (node (ref "U1") (pin "18") (pinfunction "RC7/RX/DT_18") (pintype "bidirectional"))
      (node (ref "UART") (pin "3") (pinfunction "3_3") (pintype "passive"))
    )
    (net (code "53") (name "/STB1") (class "Default")
      (node (ref "U081") (pin "3") (pinfunction "Y_3") (pintype "output"))
      (node (ref "U1511") (pin "7") (pinfunction "~{STB}_7") (pintype "input"))
    )
    (net (code "54") (name "/STB1P") (class "Default")
      (node (ref "U081") (pin "1") (pinfunction "A_1") (pintype "input"))
      (node (ref "U081") (pin "2") (pinfunction "B_2") (pintype "input"))
      (node (ref "U1") (pin "24") (pinfunction "RB3/CCP2_24") (pintype "bidirectional"))
    )
    (net (code "55") (name "/STB2") (class "Default")
      (node (ref "U082") (pin "11") (pinfunction "Y_11") (pintype "output"))
      (node (ref "U1512") (pin "7") (pinfunction "~{STB}_7") (pintype "input"))
    )
    (net (code "56") (name "/STB2P") (class "Default")
      (node (ref "U082") (pin "12") (pinfunction "A_12") (pintype "input"))
      (node (ref "U082") (pin "13") (pinfunction "B_13") (pintype "input"))
      (node (ref "U1") (pin "25") (pinfunction "RB4_25") (pintype "bidirectional"))
    )
    (net (code "57") (name "/STB3") (class "Default")
      (node (ref "U082") (pin "8") (pinfunction "Y_8") (pintype "output"))
      (node (ref "U1513") (pin "7") (pinfunction "~{STB}_7") (pintype "input"))
    )
    (net (code "58") (name "/STB3P") (class "Default")
      (node (ref "U082") (pin "10") (pinfunction "B_10") (pintype "input"))
      (node (ref "U082") (pin "9") (pinfunction "A_9") (pintype "input"))
      (node (ref "U1") (pin "26") (pinfunction "RB5/PGM_26") (pintype "bidirectional"))
    )
    (net (code "59") (name "/STB4") (class "Default")
      (node (ref "U082") (pin "6") (pinfunction "Y_6") (pintype "output"))
      (node (ref "U1514") (pin "7") (pinfunction "~{STB}_7") (pintype "input"))
    )
    (net (code "60") (name "/STB4P") (class "Default")
      (node (ref "U082") (pin "4") (pinfunction "A_4") (pintype "input"))
      (node (ref "U082") (pin "5") (pinfunction "B_5") (pintype "input"))
      (node (ref "U1") (pin "2") (pinfunction "RA0/AN0_2") (pintype "bidirectional"))
    )
    (net (code "61") (name "/STB5") (class "Default")
      (node (ref "U082") (pin "3") (pinfunction "Y_3") (pintype "output"))
      (node (ref "U1515") (pin "7") (pinfunction "~{STB}_7") (pintype "input"))
    )
    (net (code "62") (name "/STB5P") (class "Default")
      (node (ref "U082") (pin "1") (pinfunction "A_1") (pintype "input"))
      (node (ref "U082") (pin "2") (pinfunction "B_2") (pintype "input"))
      (node (ref "U1") (pin "3") (pinfunction "RA1/AN1_3") (pintype "bidirectional"))
    )
    (net (code "63") (name "/TH1") (class "Default")
      (node (ref "U1") (pin "11") (pinfunction "RC0/T1OSO/T1CKI_11") (pintype "bidirectional"))
    )
    (net (code "64") (name "/TH2") (class "Default")
      (node (ref "U1") (pin "12") (pinfunction "RC1/T1OSI/CCP2_12") (pintype "bidirectional"))
    )
    (net (code "65") (name "/TH3") (class "Default")
      (node (ref "U1") (pin "13") (pinfunction "RC2/CCP1_13") (pintype "bidirectional"))
    )
    (net (code "66") (name "/TH4") (class "Default")
      (node (ref "U1") (pin "14") (pinfunction "RC3/SCK/SCL_14") (pintype "bidirectional"))
    )
    (net (code "67") (name "/TH5") (class "Default")
      (node (ref "U1") (pin "15") (pinfunction "RC4/SDI/SDA_15") (pintype "bidirectional"))
    )
    (net (code "68") (name "/TX") (class "Default")
      (node (ref "DTX") (pin "2") (pinfunction "K_2") (pintype "passive"))
      (node (ref "U1") (pin "17") (pinfunction "RC6/TX/CK_17") (pintype "bidirectional"))
      (node (ref "UART") (pin "1") (pinfunction "1_1") (pintype "passive"))
    )
    (net (code "69") (name "GND") (class "Default")
      (node (ref "C081") (pin "2") (pinfunction "2_2") (pintype "passive"))
      (node (ref "C082") (pin "2") (pinfunction "2_2") (pintype "passive"))
      (node (ref "C1") (pin "2") (pinfunction "2_2") (pintype "passive"))
      (node (ref "C1511") (pin "2") (pinfunction "2_2") (pintype "passive"))
      (node (ref "C1512") (pin "2") (pinfunction "2_2") (pintype "passive"))
      (node (ref "C1513") (pin "2") (pinfunction "2_2") (pintype "passive"))
      (node (ref "C1514") (pin "2") (pinfunction "2_2") (pintype "passive"))
      (node (ref "C1515") (pin "2") (pinfunction "2_2") (pintype "passive"))
      (node (ref "C1P") (pin "2") (pinfunction "2_2") (pintype "passive"))
      (node (ref "C2") (pin "2") (pinfunction "2_2") (pintype "passive"))
      (node (ref "C2P") (pin "2") (pinfunction "2_2") (pintype "passive"))
      (node (ref "C3") (pin "2") (pinfunction "2_2") (pintype "passive"))
      (node (ref "DP1") (pin "2") (pinfunction "K_2") (pintype "passive"))
      (node (ref "DP2") (pin "2") (pinfunction "K_2") (pintype "passive"))
      (node (ref "PICKIT3") (pin "3") (pinfunction "3_3") (pintype "passive"))
      (node (ref "POWER") (pin "2") (pinfunction "2_2") (pintype "passive"))
      (node (ref "Rx33") (pin "1") (pinfunction "1_1") (pintype "passive"))
      (node (ref "U081") (pin "7") (pinfunction "GND_7") (pintype "power_in"))
      (node (ref "U082") (pin "7") (pinfunction "GND_7") (pintype "power_in"))
      (node (ref "U1") (pin "19") (pinfunction "VSS_19") (pintype "power_in"))
      (node (ref "U1") (pin "8") (pinfunction "VSS_8") (pintype "power_in"))
      (node (ref "U1511") (pin "8") (pinfunction "GND_8") (pintype "power_in"))
      (node (ref "U1512") (pin "8") (pinfunction "GND_8") (pintype "power_in"))
      (node (ref "U1513") (pin "8") (pinfunction "GND_8") (pintype "power_in"))
      (node (ref "U1514") (pin "8") (pinfunction "GND_8") (pintype "power_in"))
      (node (ref "U1515") (pin "8") (pinfunction "GND_8") (pintype "power_in"))
      (node (ref "U28031") (pin "9") (pinfunction "GND_9") (pintype "power_in"))
      (node (ref "U28032") (pin "9") (pinfunction "GND_9") (pintype "power_in"))
      (node (ref "U28033") (pin "9") (pinfunction "GND_9") (pintype "power_in"))
      (node (ref "U28034") (pin "9") (pinfunction "GND_9") (pintype "power_in"))
      (node (ref "U28035") (pin "9") (pinfunction "GND_9") (pintype "power_in"))
      (node (ref "UART") (pin "2") (pinfunction "2_2") (pintype "passive"))
    )
    (net (code "70") (name "Net-(DP1-A)") (class "Default")
      (node (ref "DP1") (pin "1") (pinfunction "A_1") (pintype "passive"))
      (node (ref "RP1") (pin "2") (pinfunction "2_2") (pintype "passive"))
    )
    (net (code "71") (name "Net-(DP2-A)") (class "Default")
      (node (ref "DP2") (pin "1") (pinfunction "A_1") (pintype "passive"))
      (node (ref "Rp2") (pin "2") (pinfunction "2_2") (pintype "passive"))
    )
    (net (code "72") (name "Net-(DRX-A)") (class "Default")
      (node (ref "DRX") (pin "1") (pinfunction "A_1") (pintype "passive"))
      (node (ref "RRX") (pin "2") (pinfunction "2_2") (pintype "passive"))
    )
    (net (code "73") (name "Net-(DTX-A)") (class "Default")
      (node (ref "DTX") (pin "1") (pinfunction "A_1") (pintype "passive"))
      (node (ref "RTX") (pin "2") (pinfunction "2_2") (pintype "passive"))
    )
    (net (code "74") (name "Net-(R2-Pad2)") (class "Default")
      (node (ref "R2") (pin "2") (pinfunction "2_2") (pintype "passive"))
      (node (ref "R228031") (pin "2") (pinfunction "2_2") (pintype "passive"))
    )
    (net (code "75") (name "Net-(R3-Pad2)") (class "Default")
      (node (ref "R3") (pin "2") (pinfunction "2_2") (pintype "passive"))
      (node (ref "R328031") (pin "2") (pinfunction "2_2") (pintype "passive"))
    )
    (net (code "76") (name "Net-(R4-Pad2)") (class "Default")
      (node (ref "R4") (pin "2") (pinfunction "2_2") (pintype "passive"))
      (node (ref "R428031") (pin "2") (pinfunction "2_2") (pintype "passive"))
    )
    (net (code "77") (name "Net-(R5-Pad2)") (class "Default")
      (node (ref "R5") (pin "2") (pinfunction "2_2") (pintype "passive"))
      (node (ref "R528031") (pin "2") (pinfunction "2_2") (pintype "passive"))
    )
    (net (code "78") (name "Net-(R6-Pad2)") (class "Default")
      (node (ref "R6") (pin "2") (pinfunction "2_2") (pintype "passive"))
      (node (ref "R628031") (pin "2") (pinfunction "2_2") (pintype "passive"))
    )
    (net (code "79") (name "Net-(R7-Pad2)") (class "Default")
      (node (ref "R7") (pin "2") (pinfunction "2_2") (pintype "passive"))
      (node (ref "R728031") (pin "2") (pinfunction "2_2") (pintype "passive"))
    )
    (net (code "80") (name "Net-(R8-Pad2)") (class "Default")
      (node (ref "R8") (pin "2") (pinfunction "2_2") (pintype "passive"))
      (node (ref "R828031") (pin "2") (pinfunction "2_2") (pintype "passive"))
    )
    (net (code "81") (name "Net-(R10-Pad2)") (class "Default")
      (node (ref "R10") (pin "2") (pinfunction "2_2") (pintype "passive"))
      (node (ref "R228032") (pin "2") (pinfunction "2_2") (pintype "passive"))
    )
    (net (code "82") (name "Net-(R11-Pad2)") (class "Default")
      (node (ref "R11") (pin "2") (pinfunction "2_2") (pintype "passive"))
      (node (ref "R328032") (pin "2") (pinfunction "2_2") (pintype "passive"))
    )
    (net (code "83") (name "Net-(R12-Pad2)") (class "Default")
      (node (ref "R12") (pin "2") (pinfunction "2_2") (pintype "passive"))
      (node (ref "R42802") (pin "2") (pinfunction "2_2") (pintype "passive"))
    )
    (net (code "84") (name "Net-(R13-Pad2)") (class "Default")
      (node (ref "R13") (pin "2") (pinfunction "2_2") (pintype "passive"))
      (node (ref "R528032") (pin "2") (pinfunction "2_2") (pintype "passive"))
    )
    (net (code "85") (name "Net-(R14-Pad2)") (class "Default")
      (node (ref "R14") (pin "2") (pinfunction "2_2") (pintype "passive"))
      (node (ref "R628032") (pin "2") (pinfunction "2_2") (pintype "passive"))
    )
    (net (code "86") (name "Net-(R15-Pad2)") (class "Default")
      (node (ref "R15") (pin "2") (pinfunction "2_2") (pintype "passive"))
      (node (ref "R728032") (pin "2") (pinfunction "2_2") (pintype "passive"))
    )
    (net (code "87") (name "Net-(R16-Pad2)") (class "Default")
      (node (ref "R16") (pin "2") (pinfunction "2_2") (pintype "passive"))
      (node (ref "R828032") (pin "2") (pinfunction "2_2") (pintype "passive"))
    )
    (net (code "88") (name "Net-(R18-Pad2)") (class "Default")
      (node (ref "R18") (pin "2") (pinfunction "2_2") (pintype "passive"))
      (node (ref "R228033") (pin "2") (pinfunction "2_2") (pintype "passive"))
    )
    (net (code "89") (name "Net-(R19-Pad2)") (class "Default")
      (node (ref "R19") (pin "2") (pinfunction "2_2") (pintype "passive"))
      (node (ref "R328033") (pin "2") (pinfunction "2_2") (pintype "passive"))
    )
    (net (code "90") (name "Net-(R20-Pad2)") (class "Default")
      (node (ref "R20") (pin "2") (pinfunction "2_2") (pintype "passive"))
      (node (ref "R42803") (pin "2") (pinfunction "2_2") (pintype "passive"))
    )
    (net (code "91") (name "Net-(R21-Pad2)") (class "Default")
      (node (ref "R21") (pin "2") (pinfunction "2_2") (pintype "passive"))
      (node (ref "R528033") (pin "2") (pinfunction "2_2") (pintype "passive"))
    )
    (net (code "92") (name "Net-(R22-Pad2)") (class "Default")
      (node (ref "R22") (pin "2") (pinfunction "2_2") (pintype "passive"))
      (node (ref "R628033") (pin "2") (pinfunction "2_2") (pintype "passive"))
    )
    (net (code "93") (name "Net-(R23-Pad2)") (class "Default")
      (node (ref "R23") (pin "2") (pinfunction "2_2") (pintype "passive"))
      (node (ref "R728033") (pin "2") (pinfunction "2_2") (pintype "passive"))
    )
    (net (code "94") (name "Net-(R24-Pad2)") (class "Default")
      (node (ref "R24") (pin "2") (pinfunction "2_2") (pintype "passive"))
      (node (ref "R828033") (pin "2") (pinfunction "2_2") (pintype "passive"))
    )
    (net (code "95") (name "Net-(R27-Pad2)") (class "Default")
      (node (ref "R27") (pin "2") (pinfunction "2_2") (pintype "passive"))
      (node (ref "R328034") (pin "2") (pinfunction "2_2") (pintype "passive"))
    )
    (net (code "96") (name "Net-(R28-Pad2)") (class "Default")
      (node (ref "R28") (pin "2") (pinfunction "2_2") (pintype "passive"))
      (node (ref "R42804") (pin "2") (pinfunction "2_2") (pintype "passive"))
    )
    (net (code "97") (name "Net-(R29-Pad2)") (class "Default")
      (node (ref "R29") (pin "2") (pinfunction "2_2") (pintype "passive"))
      (node (ref "R528034") (pin "2") (pinfunction "2_2") (pintype "passive"))
    )
    (net (code "98") (name "Net-(R30-Pad2)") (class "Default")
      (node (ref "R30") (pin "2") (pinfunction "2_2") (pintype "passive"))
      (node (ref "R628034") (pin "2") (pinfunction "2_2") (pintype "passive"))
    )
    (net (code "99") (name "Net-(R31-Pad2)") (class "Default")
      (node (ref "R31") (pin "2") (pinfunction "2_2") (pintype "passive"))
      (node (ref "R728034") (pin "2") (pinfunction "2_2") (pintype "passive"))
    )
    (net (code "100") (name "Net-(R32-Pad2)") (class "Default")
      (node (ref "R32") (pin "2") (pinfunction "2_2") (pintype "passive"))
      (node (ref "R828034") (pin "2") (pinfunction "2_2") (pintype "passive"))
    )
    (net (code "101") (name "Net-(R36-Pad2)") (class "Default")
      (node (ref "R36") (pin "2") (pinfunction "2_2") (pintype "passive"))
      (node (ref "R428035") (pin "2") (pinfunction "2_2") (pintype "passive"))
    )
    (net (code "102") (name "Net-(R37-Pad2)") (class "Default")
      (node (ref "R37") (pin "2") (pinfunction "2_2") (pintype "passive"))
      (node (ref "R528035") (pin "2") (pinfunction "2_2") (pintype "passive"))
    )
    (net (code "103") (name "Net-(R38-Pad2)") (class "Default")
      (node (ref "R38") (pin "2") (pinfunction "2_2") (pintype "passive"))
      (node (ref "R628035") (pin "2") (pinfunction "2_2") (pintype "passive"))
    )
    (net (code "104") (name "Net-(R39-Pad2)") (class "Default")
      (node (ref "R39") (pin "2") (pinfunction "2_2") (pintype "passive"))
      (node (ref "R728035") (pin "2") (pinfunction "2_2") (pintype "passive"))
    )
    (net (code "105") (name "Net-(R40-Pad2)") (class "Default")
      (node (ref "R40") (pin "2") (pinfunction "2_2") (pintype "passive"))
      (node (ref "R828035") (pin "2") (pinfunction "2_2") (pintype "passive"))
    )
    (net (code "106") (name "Net-(R111-Pad2)") (class "Default")
      (node (ref "R111") (pin "2") (pinfunction "2_2") (pintype "passive"))
      (node (ref "R128031") (pin "2") (pinfunction "2_2") (pintype "passive"))
    )
    (net (code "107") (name "Net-(R128032-Pad2)") (class "Default")
      (node (ref "R128032") (pin "2") (pinfunction "2_2") (pintype "passive"))
      (node (ref "R9") (pin "2") (pinfunction "2_2") (pintype "passive"))
    )
    (net (code "108") (name "Net-(R128033-Pad2)") (class "Default")
      (node (ref "R128033") (pin "2") (pinfunction "2_2") (pintype "passive"))
      (node (ref "R17") (pin "2") (pinfunction "2_2") (pintype "passive"))
    )
    (net (code "109") (name "Net-(R128034-Pad2)") (class "Default")
      (node (ref "R128034") (pin "2") (pinfunction "2_2") (pintype "passive"))
      (node (ref "R25") (pin "2") (pinfunction "2_2") (pintype "passive"))
    )
    (net (code "110") (name "Net-(R128035-Pad2)") (class "Default")
      (node (ref "R128035") (pin "2") (pinfunction "2_2") (pintype "passive"))
      (node (ref "R33") (pin "2") (pinfunction "2_2") (pintype "passive"))
    )
    (net (code "111") (name "Net-(R228034-Pad2)") (class "Default")
      (node (ref "R228034") (pin "2") (pinfunction "2_2") (pintype "passive"))
      (node (ref "R26") (pin "2") (pinfunction "2_2") (pintype "passive"))
    )
    (net (code "112") (name "Net-(R228035-Pad2)") (class "Default")
      (node (ref "R228035") (pin "2") (pinfunction "2_2") (pintype "passive"))
      (node (ref "R34") (pin "2") (pinfunction "2_2") (pintype "passive"))
    )
    (net (code "113") (name "Net-(R328035-Pad2)") (class "Default")
      (node (ref "R328035") (pin "2") (pinfunction "2_2") (pintype "passive"))
      (node (ref "R35") (pin "2") (pinfunction "2_2") (pintype "passive"))
    )
    (net (code "114") (name "Net-(U1-OSC1{slash}CLKI)") (class "Default")
      (node (ref "C3") (pin "1") (pinfunction "1_1") (pintype "passive"))
      (node (ref "U1") (pin "9") (pinfunction "OSC1/CLKI_9") (pintype "input"))
      (node (ref "Y1") (pin "1") (pinfunction "OSC1_1") (pintype "passive"))
    )
    (net (code "115") (name "Net-(U1-OSC2{slash}CLKO{slash}RA6)") (class "Default")
      (node (ref "C2") (pin "1") (pinfunction "1_1") (pintype "passive"))
      (node (ref "U1") (pin "10") (pinfunction "OSC2/CLKO/RA6_10") (pintype "bidirectional"))
      (node (ref "Y1") (pin "2") (pinfunction "OSC2_2") (pintype "passive"))
    )
    (net (code "116") (name "Net-(U1511-D0)") (class "Default")
      (node (ref "P031") (pin "1") (pinfunction "1_1") (pintype "passive"))
      (node (ref "U1511") (pin "4") (pinfunction "D0_4") (pintype "input"))
      (node (ref "U28031") (pin "18") (pinfunction "OUT1_18") (pintype "open_collector"))
    )
    (net (code "117") (name "Net-(U1511-D1)") (class "Default")
      (node (ref "P031") (pin "2") (pinfunction "2_2") (pintype "passive"))
      (node (ref "U1511") (pin "3") (pinfunction "D1_3") (pintype "input"))
      (node (ref "U28031") (pin "17") (pinfunction "OUT2_17") (pintype "open_collector"))
    )
    (net (code "118") (name "Net-(U1511-D2)") (class "Default")
      (node (ref "P031") (pin "3") (pinfunction "3_3") (pintype "passive"))
      (node (ref "U1511") (pin "2") (pinfunction "D2_2") (pintype "input"))
      (node (ref "U28031") (pin "16") (pinfunction "OUT3_16") (pintype "open_collector"))
    )
    (net (code "119") (name "Net-(U1511-D3)") (class "Default")
      (node (ref "P031") (pin "4") (pinfunction "4_4") (pintype "passive"))
      (node (ref "U1511") (pin "1") (pinfunction "D3_1") (pintype "input"))
      (node (ref "U28031") (pin "15") (pinfunction "OUT4_15") (pintype "open_collector"))
    )
    (net (code "120") (name "Net-(U1511-D4)") (class "Default")
      (node (ref "P031") (pin "5") (pinfunction "5_5") (pintype "passive"))
      (node (ref "U1511") (pin "15") (pinfunction "D4_15") (pintype "input"))
      (node (ref "U28031") (pin "14") (pinfunction "OUT5_14") (pintype "open_collector"))
    )
    (net (code "121") (name "Net-(U1511-D5)") (class "Default")
      (node (ref "P031") (pin "6") (pinfunction "6_6") (pintype "passive"))
      (node (ref "U1511") (pin "14") (pinfunction "D5_14") (pintype "input"))
      (node (ref "U28031") (pin "13") (pinfunction "OUT6_13") (pintype "open_collector"))
    )
    (net (code "122") (name "Net-(U1511-D6)") (class "Default")
      (node (ref "P031") (pin "7") (pinfunction "7_7") (pintype "passive"))
      (node (ref "U1511") (pin "13") (pinfunction "D6_13") (pintype "input"))
      (node (ref "U28031") (pin "12") (pinfunction "OUT7_12") (pintype "open_collector"))
    )
    (net (code "123") (name "Net-(U1511-D7)") (class "Default")
      (node (ref "P031") (pin "8") (pinfunction "8_8") (pintype "passive"))
      (node (ref "U1511") (pin "12") (pinfunction "D7_12") (pintype "input"))
      (node (ref "U28031") (pin "11") (pinfunction "OUT8_11") (pintype "open_collector"))
    )
    (net (code "124") (name "Net-(U1512-D0)") (class "Default")
      (node (ref "P032") (pin "1") (pinfunction "1_1") (pintype "passive"))
      (node (ref "U1512") (pin "4") (pinfunction "D0_4") (pintype "input"))
      (node (ref "U28032") (pin "18") (pinfunction "OUT1_18") (pintype "open_collector"))
    )
    (net (code "125") (name "Net-(U1512-D1)") (class "Default")
      (node (ref "P032") (pin "2") (pinfunction "2_2") (pintype "passive"))
      (node (ref "U1512") (pin "3") (pinfunction "D1_3") (pintype "input"))
      (node (ref "U28032") (pin "17") (pinfunction "OUT2_17") (pintype "open_collector"))
    )
    (net (code "126") (name "Net-(U1512-D2)") (class "Default")
      (node (ref "P032") (pin "3") (pinfunction "3_3") (pintype "passive"))
      (node (ref "U1512") (pin "2") (pinfunction "D2_2") (pintype "input"))
      (node (ref "U28032") (pin "16") (pinfunction "OUT3_16") (pintype "open_collector"))
    )
    (net (code "127") (name "Net-(U1512-D3)") (class "Default")
      (node (ref "P032") (pin "4") (pinfunction "4_4") (pintype "passive"))
      (node (ref "U1512") (pin "1") (pinfunction "D3_1") (pintype "input"))
      (node (ref "U28032") (pin "15") (pinfunction "OUT4_15") (pintype "open_collector"))
    )
    (net (code "128") (name "Net-(U1512-D4)") (class "Default")
      (node (ref "P032") (pin "5") (pinfunction "5_5") (pintype "passive"))
      (node (ref "U1512") (pin "15") (pinfunction "D4_15") (pintype "input"))
      (node (ref "U28032") (pin "14") (pinfunction "OUT5_14") (pintype "open_collector"))
    )
    (net (code "129") (name "Net-(U1512-D5)") (class "Default")
      (node (ref "P032") (pin "6") (pinfunction "6_6") (pintype "passive"))
      (node (ref "U1512") (pin "14") (pinfunction "D5_14") (pintype "input"))
      (node (ref "U28032") (pin "13") (pinfunction "OUT6_13") (pintype "open_collector"))
    )
    (net (code "130") (name "Net-(U1512-D6)") (class "Default")
      (node (ref "P032") (pin "7") (pinfunction "7_7") (pintype "passive"))
      (node (ref "U1512") (pin "13") (pinfunction "D6_13") (pintype "input"))
      (node (ref "U28032") (pin "12") (pinfunction "OUT7_12") (pintype "open_collector"))
    )
    (net (code "131") (name "Net-(U1512-D7)") (class "Default")
      (node (ref "P032") (pin "8") (pinfunction "8_8") (pintype "passive"))
      (node (ref "U1512") (pin "12") (pinfunction "D7_12") (pintype "input"))
      (node (ref "U28032") (pin "11") (pinfunction "OUT8_11") (pintype "open_collector"))
    )
    (net (code "132") (name "Net-(U1513-D0)") (class "Default")
      (node (ref "P033") (pin "1") (pinfunction "1_1") (pintype "passive"))
      (node (ref "U1513") (pin "4") (pinfunction "D0_4") (pintype "input"))
      (node (ref "U28033") (pin "18") (pinfunction "OUT1_18") (pintype "open_collector"))
    )
    (net (code "133") (name "Net-(U1513-D1)") (class "Default")
      (node (ref "P033") (pin "2") (pinfunction "2_2") (pintype "passive"))
      (node (ref "U1513") (pin "3") (pinfunction "D1_3") (pintype "input"))
      (node (ref "U28033") (pin "17") (pinfunction "OUT2_17") (pintype "open_collector"))
    )
    (net (code "134") (name "Net-(U1513-D2)") (class "Default")
      (node (ref "P033") (pin "3") (pinfunction "3_3") (pintype "passive"))
      (node (ref "U1513") (pin "2") (pinfunction "D2_2") (pintype "input"))
      (node (ref "U28033") (pin "16") (pinfunction "OUT3_16") (pintype "open_collector"))
    )
    (net (code "135") (name "Net-(U1513-D3)") (class "Default")
      (node (ref "P033") (pin "4") (pinfunction "4_4") (pintype "passive"))
      (node (ref "U1513") (pin "1") (pinfunction "D3_1") (pintype "input"))
      (node (ref "U28033") (pin "15") (pinfunction "OUT4_15") (pintype "open_collector"))
    )
    (net (code "136") (name "Net-(U1513-D4)") (class "Default")
      (node (ref "P033") (pin "5") (pinfunction "5_5") (pintype "passive"))
      (node (ref "U1513") (pin "15") (pinfunction "D4_15") (pintype "input"))
      (node (ref "U28033") (pin "14") (pinfunction "OUT5_14") (pintype "open_collector"))
    )
    (net (code "137") (name "Net-(U1513-D5)") (class "Default")
      (node (ref "P033") (pin "6") (pinfunction "6_6") (pintype "passive"))
      (node (ref "U1513") (pin "14") (pinfunction "D5_14") (pintype "input"))
      (node (ref "U28033") (pin "13") (pinfunction "OUT6_13") (pintype "open_collector"))
    )
    (net (code "138") (name "Net-(U1513-D6)") (class "Default")
      (node (ref "P033") (pin "7") (pinfunction "7_7") (pintype "passive"))
      (node (ref "U1513") (pin "13") (pinfunction "D6_13") (pintype "input"))
      (node (ref "U28033") (pin "12") (pinfunction "OUT7_12") (pintype "open_collector"))
    )
    (net (code "139") (name "Net-(U1513-D7)") (class "Default")
      (node (ref "P033") (pin "8") (pinfunction "8_8") (pintype "passive"))
      (node (ref "U1513") (pin "12") (pinfunction "D7_12") (pintype "input"))
      (node (ref "U28033") (pin "11") (pinfunction "OUT8_11") (pintype "open_collector"))
    )
    (net (code "140") (name "Net-(U1514-D0)") (class "Default")
      (node (ref "P034") (pin "1") (pinfunction "1_1") (pintype "passive"))
      (node (ref "U1514") (pin "4") (pinfunction "D0_4") (pintype "input"))
      (node (ref "U28034") (pin "18") (pinfunction "OUT1_18") (pintype "open_collector"))
    )
    (net (code "141") (name "Net-(U1514-D1)") (class "Default")
      (node (ref "P034") (pin "2") (pinfunction "2_2") (pintype "passive"))
      (node (ref "U1514") (pin "3") (pinfunction "D1_3") (pintype "input"))
      (node (ref "U28034") (pin "17") (pinfunction "OUT2_17") (pintype "open_collector"))
    )
    (net (code "142") (name "Net-(U1514-D2)") (class "Default")
      (node (ref "P034") (pin "3") (pinfunction "3_3") (pintype "passive"))
      (node (ref "U1514") (pin "2") (pinfunction "D2_2") (pintype "input"))
      (node (ref "U28034") (pin "16") (pinfunction "OUT3_16") (pintype "open_collector"))
    )
    (net (code "143") (name "Net-(U1514-D3)") (class "Default")
      (node (ref "P034") (pin "4") (pinfunction "4_4") (pintype "passive"))
      (node (ref "U1514") (pin "1") (pinfunction "D3_1") (pintype "input"))
      (node (ref "U28034") (pin "15") (pinfunction "OUT4_15") (pintype "open_collector"))
    )
    (net (code "144") (name "Net-(U1514-D4)") (class "Default")
      (node (ref "P034") (pin "5") (pinfunction "5_5") (pintype "passive"))
      (node (ref "U1514") (pin "15") (pinfunction "D4_15") (pintype "input"))
      (node (ref "U28034") (pin "14") (pinfunction "OUT5_14") (pintype "open_collector"))
    )
    (net (code "145") (name "Net-(U1514-D5)") (class "Default")
      (node (ref "P034") (pin "6") (pinfunction "6_6") (pintype "passive"))
      (node (ref "U1514") (pin "14") (pinfunction "D5_14") (pintype "input"))
      (node (ref "U28034") (pin "13") (pinfunction "OUT6_13") (pintype "open_collector"))
    )
    (net (code "146") (name "Net-(U1514-D6)") (class "Default")
      (node (ref "P034") (pin "7") (pinfunction "7_7") (pintype "passive"))
      (node (ref "U1514") (pin "13") (pinfunction "D6_13") (pintype "input"))
      (node (ref "U28034") (pin "12") (pinfunction "OUT7_12") (pintype "open_collector"))
    )
    (net (code "147") (name "Net-(U1514-D7)") (class "Default")
      (node (ref "P034") (pin "8") (pinfunction "8_8") (pintype "passive"))
      (node (ref "U1514") (pin "12") (pinfunction "D7_12") (pintype "input"))
      (node (ref "U28034") (pin "11") (pinfunction "OUT8_11") (pintype "open_collector"))
    )
    (net (code "148") (name "Net-(U1515-D0)") (class "Default")
      (node (ref "P035") (pin "1") (pinfunction "1_1") (pintype "passive"))
      (node (ref "U1515") (pin "4") (pinfunction "D0_4") (pintype "input"))
      (node (ref "U28035") (pin "18") (pinfunction "OUT1_18") (pintype "open_collector"))
    )
    (net (code "149") (name "Net-(U1515-D1)") (class "Default")
      (node (ref "P035") (pin "2") (pinfunction "2_2") (pintype "passive"))
      (node (ref "U1515") (pin "3") (pinfunction "D1_3") (pintype "input"))
      (node (ref "U28035") (pin "17") (pinfunction "OUT2_17") (pintype "open_collector"))
    )
    (net (code "150") (name "Net-(U1515-D2)") (class "Default")
      (node (ref "P035") (pin "3") (pinfunction "3_3") (pintype "passive"))
      (node (ref "U1515") (pin "2") (pinfunction "D2_2") (pintype "input"))
      (node (ref "U28035") (pin "16") (pinfunction "OUT3_16") (pintype "open_collector"))
    )
    (net (code "151") (name "Net-(U1515-D3)") (class "Default")
      (node (ref "P035") (pin "4") (pinfunction "4_4") (pintype "passive"))
      (node (ref "U1515") (pin "1") (pinfunction "D3_1") (pintype "input"))
      (node (ref "U28035") (pin "15") (pinfunction "OUT4_15") (pintype "open_collector"))
    )
    (net (code "152") (name "Net-(U1515-D4)") (class "Default")
      (node (ref "P035") (pin "5") (pinfunction "5_5") (pintype "passive"))
      (node (ref "U1515") (pin "15") (pinfunction "D4_15") (pintype "input"))
      (node (ref "U28035") (pin "14") (pinfunction "OUT5_14") (pintype "open_collector"))
    )
    (net (code "153") (name "Net-(U1515-D5)") (class "Default")
      (node (ref "P035") (pin "6") (pinfunction "6_6") (pintype "passive"))
      (node (ref "U1515") (pin "14") (pinfunction "D5_14") (pintype "input"))
      (node (ref "U28035") (pin "13") (pinfunction "OUT6_13") (pintype "open_collector"))
    )
    (net (code "154") (name "Net-(U1515-D6)") (class "Default")
      (node (ref "P035") (pin "7") (pinfunction "7_7") (pintype "passive"))
      (node (ref "U1515") (pin "13") (pinfunction "D6_13") (pintype "input"))
      (node (ref "U28035") (pin "12") (pinfunction "OUT7_12") (pintype "open_collector"))
    )
    (net (code "155") (name "Net-(U1515-D7)") (class "Default")
      (node (ref "P035") (pin "8") (pinfunction "8_8") (pintype "passive"))
      (node (ref "U1515") (pin "12") (pinfunction "D7_12") (pintype "input"))
      (node (ref "U28035") (pin "11") (pinfunction "OUT8_11") (pintype "open_collector"))
    )
    (net (code "156") (name "Net-(U28031-IN1)") (class "Default")
      (node (ref "R128031") (pin "1") (pinfunction "1_1") (pintype "passive"))
      (node (ref "U28031") (pin "1") (pinfunction "IN1_1") (pintype "input"))
    )
    (net (code "157") (name "Net-(U28031-IN2)") (class "Default")
      (node (ref "R228031") (pin "1") (pinfunction "1_1") (pintype "passive"))
      (node (ref "U28031") (pin "2") (pinfunction "IN2_2") (pintype "input"))
    )
    (net (code "158") (name "Net-(U28031-IN3)") (class "Default")
      (node (ref "R328031") (pin "1") (pinfunction "1_1") (pintype "passive"))
      (node (ref "U28031") (pin "3") (pinfunction "IN3_3") (pintype "input"))
    )
    (net (code "159") (name "Net-(U28031-IN4)") (class "Default")
      (node (ref "R428031") (pin "1") (pinfunction "1_1") (pintype "passive"))
      (node (ref "U28031") (pin "4") (pinfunction "IN4_4") (pintype "input"))
    )
    (net (code "160") (name "Net-(U28031-IN5)") (class "Default")
      (node (ref "R528031") (pin "1") (pinfunction "1_1") (pintype "passive"))
      (node (ref "U28031") (pin "5") (pinfunction "IN5_5") (pintype "input"))
    )
    (net (code "161") (name "Net-(U28031-IN6)") (class "Default")
      (node (ref "R628031") (pin "1") (pinfunction "1_1") (pintype "passive"))
      (node (ref "U28031") (pin "6") (pinfunction "IN6_6") (pintype "input"))
    )
    (net (code "162") (name "Net-(U28031-IN7)") (class "Default")
      (node (ref "R728031") (pin "1") (pinfunction "1_1") (pintype "passive"))
      (node (ref "U28031") (pin "7") (pinfunction "IN7_7") (pintype "input"))
    )
    (net (code "163") (name "Net-(U28031-IN8)") (class "Default")
      (node (ref "R828031") (pin "1") (pinfunction "1_1") (pintype "passive"))
      (node (ref "U28031") (pin "8") (pinfunction "IN8_8") (pintype "input"))
    )
    (net (code "164") (name "Net-(U28032-IN1)") (class "Default")
      (node (ref "R128032") (pin "1") (pinfunction "1_1") (pintype "passive"))
      (node (ref "U28032") (pin "1") (pinfunction "IN1_1") (pintype "input"))
    )
    (net (code "165") (name "Net-(U28032-IN2)") (class "Default")
      (node (ref "R228032") (pin "1") (pinfunction "1_1") (pintype "passive"))
      (node (ref "U28032") (pin "2") (pinfunction "IN2_2") (pintype "input"))
    )
    (net (code "166") (name "Net-(U28032-IN3)") (class "Default")
      (node (ref "R328032") (pin "1") (pinfunction "1_1") (pintype "passive"))
      (node (ref "U28032") (pin "3") (pinfunction "IN3_3") (pintype "input"))
    )
    (net (code "167") (name "Net-(U28032-IN4)") (class "Default")
      (node (ref "R42802") (pin "1") (pinfunction "1_1") (pintype "passive"))
      (node (ref "U28032") (pin "4") (pinfunction "IN4_4") (pintype "input"))
    )
    (net (code "168") (name "Net-(U28032-IN5)") (class "Default")
      (node (ref "R528032") (pin "1") (pinfunction "1_1") (pintype "passive"))
      (node (ref "U28032") (pin "5") (pinfunction "IN5_5") (pintype "input"))
    )
    (net (code "169") (name "Net-(U28032-IN6)") (class "Default")
      (node (ref "R628032") (pin "1") (pinfunction "1_1") (pintype "passive"))
      (node (ref "U28032") (pin "6") (pinfunction "IN6_6") (pintype "input"))
    )
    (net (code "170") (name "Net-(U28032-IN7)") (class "Default")
      (node (ref "R728032") (pin "1") (pinfunction "1_1") (pintype "passive"))
      (node (ref "U28032") (pin "7") (pinfunction "IN7_7") (pintype "input"))
    )
    (net (code "171") (name "Net-(U28032-IN8)") (class "Default")
      (node (ref "R828032") (pin "1") (pinfunction "1_1") (pintype "passive"))
      (node (ref "U28032") (pin "8") (pinfunction "IN8_8") (pintype "input"))
    )
    (net (code "172") (name "Net-(U28033-IN1)") (class "Default")
      (node (ref "R128033") (pin "1") (pinfunction "1_1") (pintype "passive"))
      (node (ref "U28033") (pin "1") (pinfunction "IN1_1") (pintype "input"))
    )
    (net (code "173") (name "Net-(U28033-IN2)") (class "Default")
      (node (ref "R228033") (pin "1") (pinfunction "1_1") (pintype "passive"))
      (node (ref "U28033") (pin "2") (pinfunction "IN2_2") (pintype "input"))
    )
    (net (code "174") (name "Net-(U28033-IN3)") (class "Default")
      (node (ref "R328033") (pin "1") (pinfunction "1_1") (pintype "passive"))
      (node (ref "U28033") (pin "3") (pinfunction "IN3_3") (pintype "input"))
    )
    (net (code "175") (name "Net-(U28033-IN4)") (class "Default")
      (node (ref "R42803") (pin "1") (pinfunction "1_1") (pintype "passive"))
      (node (ref "U28033") (pin "4") (pinfunction "IN4_4") (pintype "input"))
    )
    (net (code "176") (name "Net-(U28033-IN5)") (class "Default")
      (node (ref "R528033") (pin "1") (pinfunction "1_1") (pintype "passive"))
      (node (ref "U28033") (pin "5") (pinfunction "IN5_5") (pintype "input"))
    )
    (net (code "177") (name "Net-(U28033-IN6)") (class "Default")
      (node (ref "R628033") (pin "1") (pinfunction "1_1") (pintype "passive"))
      (node (ref "U28033") (pin "6") (pinfunction "IN6_6") (pintype "input"))
    )
    (net (code "178") (name "Net-(U28033-IN7)") (class "Default")
      (node (ref "R728033") (pin "1") (pinfunction "1_1") (pintype "passive"))
      (node (ref "U28033") (pin "7") (pinfunction "IN7_7") (pintype "input"))
    )
    (net (code "179") (name "Net-(U28033-IN8)") (class "Default")
      (node (ref "R828033") (pin "1") (pinfunction "1_1") (pintype "passive"))
      (node (ref "U28033") (pin "8") (pinfunction "IN8_8") (pintype "input"))
    )
    (net (code "180") (name "Net-(U28034-IN1)") (class "Default")
      (node (ref "R128034") (pin "1") (pinfunction "1_1") (pintype "passive"))
      (node (ref "U28034") (pin "1") (pinfunction "IN1_1") (pintype "input"))
    )
    (net (code "181") (name "Net-(U28034-IN2)") (class "Default")
      (node (ref "R228034") (pin "1") (pinfunction "1_1") (pintype "passive"))
      (node (ref "U28034") (pin "2") (pinfunction "IN2_2") (pintype "input"))
    )
    (net (code "182") (name "Net-(U28034-IN3)") (class "Default")
      (node (ref "R328034") (pin "1") (pinfunction "1_1") (pintype "passive"))
      (node (ref "U28034") (pin "3") (pinfunction "IN3_3") (pintype "input"))
    )
    (net (code "183") (name "Net-(U28034-IN4)") (class "Default")
      (node (ref "R42804") (pin "1") (pinfunction "1_1") (pintype "passive"))
      (node (ref "U28034") (pin "4") (pinfunction "IN4_4") (pintype "input"))
    )
    (net (code "184") (name "Net-(U28034-IN5)") (class "Default")
      (node (ref "R528034") (pin "1") (pinfunction "1_1") (pintype "passive"))
      (node (ref "U28034") (pin "5") (pinfunction "IN5_5") (pintype "input"))
    )
    (net (code "185") (name "Net-(U28034-IN6)") (class "Default")
      (node (ref "R628034") (pin "1") (pinfunction "1_1") (pintype "passive"))
      (node (ref "U28034") (pin "6") (pinfunction "IN6_6") (pintype "input"))
    )
    (net (code "186") (name "Net-(U28034-IN7)") (class "Default")
      (node (ref "R728034") (pin "1") (pinfunction "1_1") (pintype "passive"))
      (node (ref "U28034") (pin "7") (pinfunction "IN7_7") (pintype "input"))
    )
    (net (code "187") (name "Net-(U28034-IN8)") (class "Default")
      (node (ref "R828034") (pin "1") (pinfunction "1_1") (pintype "passive"))
      (node (ref "U28034") (pin "8") (pinfunction "IN8_8") (pintype "input"))
    )
    (net (code "188") (name "Net-(U28035-IN1)") (class "Default")
      (node (ref "R128035") (pin "1") (pinfunction "1_1") (pintype "passive"))
      (node (ref "U28035") (pin "1") (pinfunction "IN1_1") (pintype "input"))
    )
    (net (code "189") (name "Net-(U28035-IN2)") (class "Default")
      (node (ref "R228035") (pin "1") (pinfunction "1_1") (pintype "passive"))
      (node (ref "U28035") (pin "2") (pinfunction "IN2_2") (pintype "input"))
    )
    (net (code "190") (name "Net-(U28035-IN3)") (class "Default")
      (node (ref "R328035") (pin "1") (pinfunction "1_1") (pintype "passive"))
      (node (ref "U28035") (pin "3") (pinfunction "IN3_3") (pintype "input"))
    )
    (net (code "191") (name "Net-(U28035-IN4)") (class "Default")
      (node (ref "R428035") (pin "1") (pinfunction "1_1") (pintype "passive"))
      (node (ref "U28035") (pin "4") (pinfunction "IN4_4") (pintype "input"))
    )
    (net (code "192") (name "Net-(U28035-IN5)") (class "Default")
      (node (ref "R528035") (pin "1") (pinfunction "1_1") (pintype "passive"))
      (node (ref "U28035") (pin "5") (pinfunction "IN5_5") (pintype "input"))
    )
    (net (code "193") (name "Net-(U28035-IN6)") (class "Default")
      (node (ref "R628035") (pin "1") (pinfunction "1_1") (pintype "passive"))
      (node (ref "U28035") (pin "6") (pinfunction "IN6_6") (pintype "input"))
    )
    (net (code "194") (name "Net-(U28035-IN7)") (class "Default")
      (node (ref "R728035") (pin "1") (pinfunction "1_1") (pintype "passive"))
      (node (ref "U28035") (pin "7") (pinfunction "IN7_7") (pintype "input"))
    )
    (net (code "195") (name "Net-(U28035-IN8)") (class "Default")
      (node (ref "R828035") (pin "1") (pinfunction "1_1") (pintype "passive"))
      (node (ref "U28035") (pin "8") (pinfunction "IN8_8") (pintype "input"))
    )
    (net (code "196") (name "VCC") (class "Default")
      (node (ref "C081") (pin "1") (pinfunction "1_1") (pintype "passive"))
      (node (ref "C082") (pin "1") (pinfunction "1_1") (pintype "passive"))
      (node (ref "C1511") (pin "1") (pinfunction "1_1") (pintype "passive"))
      (node (ref "C1512") (pin "1") (pinfunction "1_1") (pintype "passive"))
      (node (ref "C1513") (pin "1") (pinfunction "1_1") (pintype "passive"))
      (node (ref "C1514") (pin "1") (pinfunction "1_1") (pintype "passive"))
      (node (ref "C1515") (pin "1") (pinfunction "1_1") (pintype "passive"))
      (node (ref "C1P") (pin "1") (pinfunction "1_1") (pintype "passive"))
      (node (ref "P031") (pin "9") (pinfunction "9_9") (pintype "passive"))
      (node (ref "P032") (pin "9") (pinfunction "9_9") (pintype "passive"))
      (node (ref "P033") (pin "9") (pinfunction "9_9") (pintype "passive"))
      (node (ref "P034") (pin "9") (pinfunction "9_9") (pintype "passive"))
      (node (ref "P035") (pin "9") (pinfunction "9_9") (pintype "passive"))
      (node (ref "POWER") (pin "1") (pinfunction "1_1") (pintype "passive"))
      (node (ref "Rp2") (pin "1") (pinfunction "1_1") (pintype "passive"))
      (node (ref "Rx21") (pin "2") (pinfunction "2_2") (pintype "passive"))
      (node (ref "U081") (pin "14") (pinfunction "VCC_14") (pintype "power_in"))
      (node (ref "U082") (pin "14") (pinfunction "VCC_14") (pintype "power_in"))
      (node (ref "U1511") (pin "16") (pinfunction "VCC_16") (pintype "power_in"))
      (node (ref "U1512") (pin "16") (pinfunction "VCC_16") (pintype "power_in"))
      (node (ref "U1513") (pin "16") (pinfunction "VCC_16") (pintype "power_in"))
      (node (ref "U1514") (pin "16") (pinfunction "VCC_16") (pintype "power_in"))
      (node (ref "U1515") (pin "16") (pinfunction "VCC_16") (pintype "power_in"))
      (node (ref "U28031") (pin "10") (pinfunction "COM_D_10") (pintype "passive"))
      (node (ref "U28032") (pin "10") (pinfunction "COM_D_10") (pintype "passive"))
      (node (ref "U28033") (pin "10") (pinfunction "COM_D_10") (pintype "passive"))
      (node (ref "U28034") (pin "10") (pinfunction "COM_D_10") (pintype "passive"))
      (node (ref "U28035") (pin "10") (pinfunction "COM_D_10") (pintype "passive"))
    )
    (net (code "197") (name "unconnected-(U1-RA2{slash}AN2{slash}VREF--Pad4)") (class "Default")
      (node (ref "U1") (pin "4") (pinfunction "RA2/AN2/VREF-_4") (pintype "bidirectional+no_connect"))
    )
    (net (code "198") (name "unconnected-(U1-RA3{slash}AN3{slash}VREF+-Pad5)") (class "Default")
      (node (ref "U1") (pin "5") (pinfunction "RA3/AN3/VREF+_5") (pintype "bidirectional+no_connect"))
    )
    (net (code "199") (name "unconnected-(U1-RA4{slash}T0CKI-Pad6)") (class "Default")
      (node (ref "U1") (pin "6") (pinfunction "RA4/T0CKI_6") (pintype "bidirectional+no_connect"))
    )
    (net (code "200") (name "unconnected-(U1-RA5{slash}AN4{slash}~{SS}{slash}LVDIN-Pad7)") (class "Default")
      (node (ref "U1") (pin "7") (pinfunction "RA5/AN4/~{SS}/LVDIN_7") (pintype "bidirectional+no_connect"))
    )
    (net (code "201") (name "unconnected-(U1-RC5{slash}SDO-Pad16)") (class "Default")
      (node (ref "U1") (pin "16") (pinfunction "RC5/SDO_16") (pintype "bidirectional"))
    )
    (net (code "202") (name "unconnected-(U1511-W-Pad6)") (class "Default")
      (node (ref "U1511") (pin "6") (pinfunction "W_6") (pintype "output"))
    )
    (net (code "203") (name "unconnected-(U1511-Y-Pad5)") (class "Default")
      (node (ref "U1511") (pin "5") (pinfunction "Y_5") (pintype "output"))
    )
    (net (code "204") (name "unconnected-(U1512-W-Pad6)") (class "Default")
      (node (ref "U1512") (pin "6") (pinfunction "W_6") (pintype "output"))
    )
    (net (code "205") (name "unconnected-(U1512-Y-Pad5)") (class "Default")
      (node (ref "U1512") (pin "5") (pinfunction "Y_5") (pintype "output"))
    )
    (net (code "206") (name "unconnected-(U1513-W-Pad6)") (class "Default")
      (node (ref "U1513") (pin "6") (pinfunction "W_6") (pintype "output"))
    )
    (net (code "207") (name "unconnected-(U1513-Y-Pad5)") (class "Default")
      (node (ref "U1513") (pin "5") (pinfunction "Y_5") (pintype "output"))
    )
    (net (code "208") (name "unconnected-(U1514-W-Pad6)") (class "Default")
      (node (ref "U1514") (pin "6") (pinfunction "W_6") (pintype "output"))
    )
    (net (code "209") (name "unconnected-(U1514-Y-Pad5)") (class "Default")
      (node (ref "U1514") (pin "5") (pinfunction "Y_5") (pintype "output"))
    )
    (net (code "210") (name "unconnected-(U1515-W-Pad6)") (class "Default")
      (node (ref "U1515") (pin "6") (pinfunction "W_6") (pintype "output"))
    )
    (net (code "211") (name "unconnected-(U1515-Y-Pad5)") (class "Default")
      (node (ref "U1515") (pin "5") (pinfunction "Y_5") (pintype "output"))
    )
  )
)
